# TIDA-010933-DCAC-TOP.net
KiCad netlist of a schematic drawn in Altium Designer
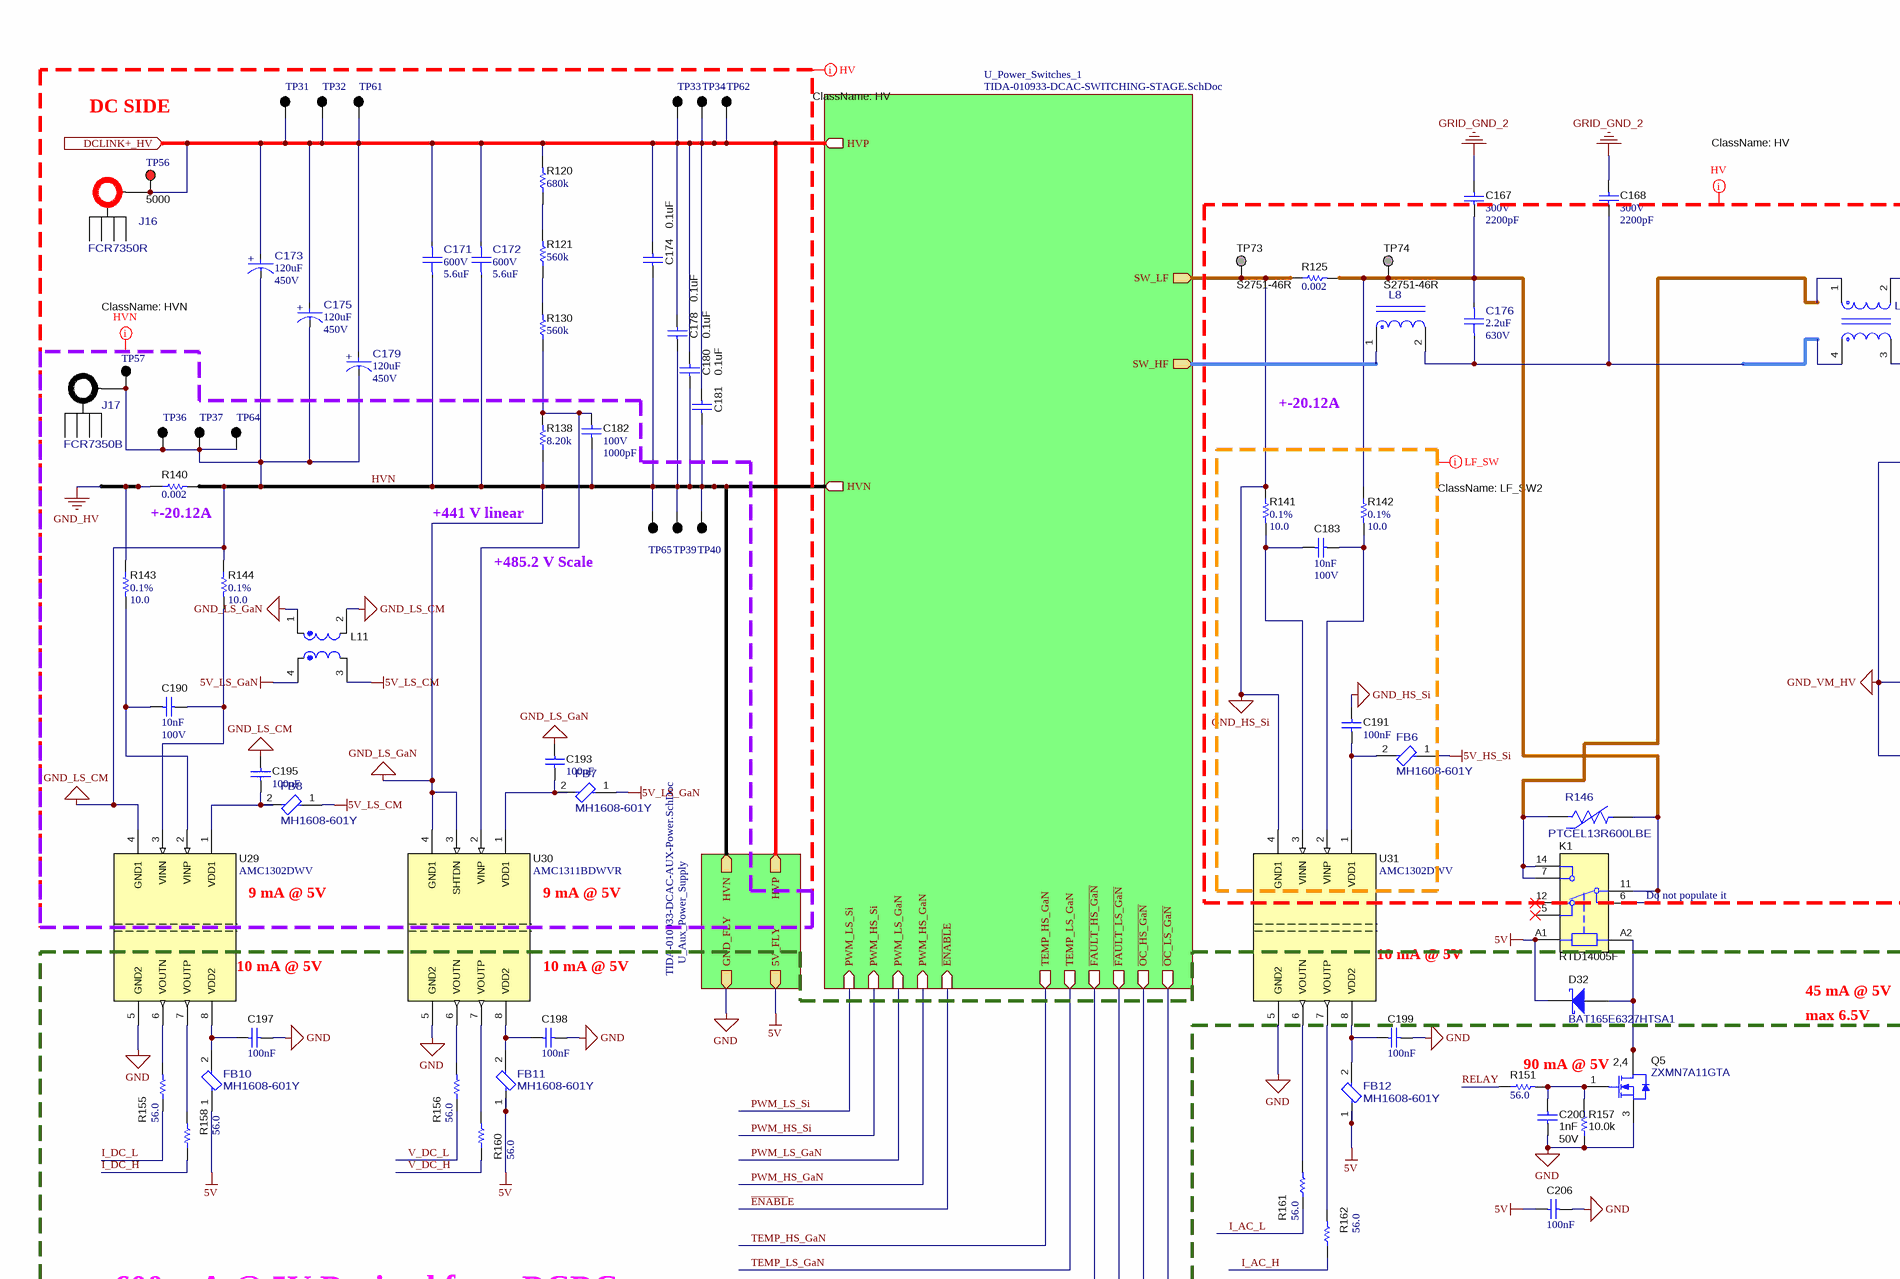
[diagram p0: TIDA-010933-DCAC-TOP.SchDoc, top left]
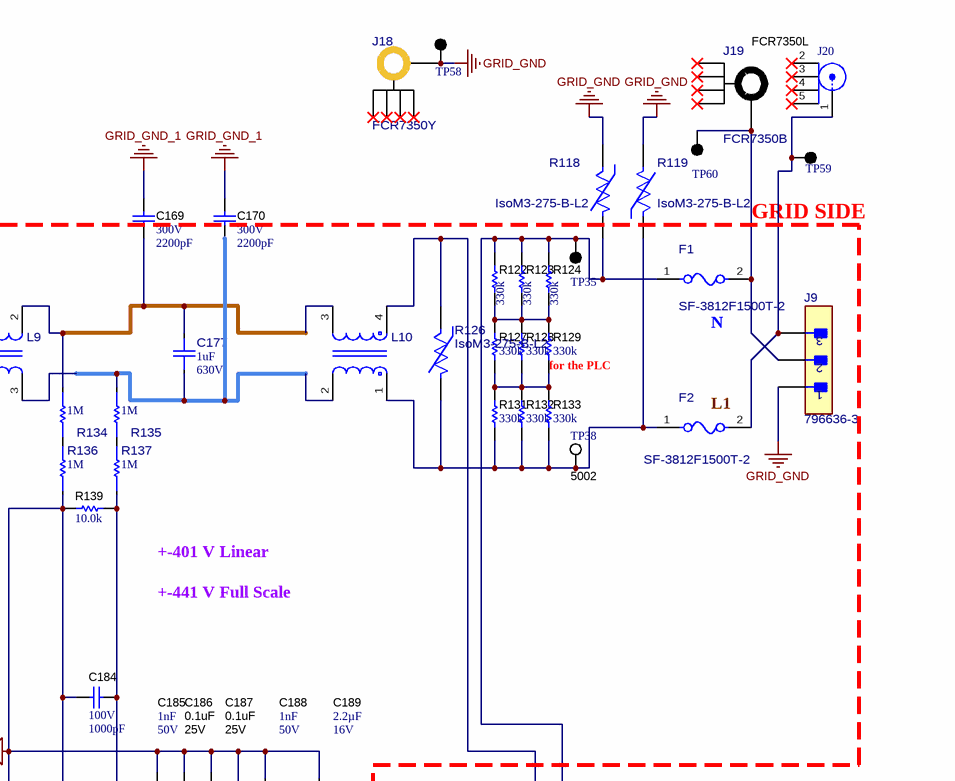
[diagram p1: TIDA-010933-DCAC-TOP.SchDoc, top right]
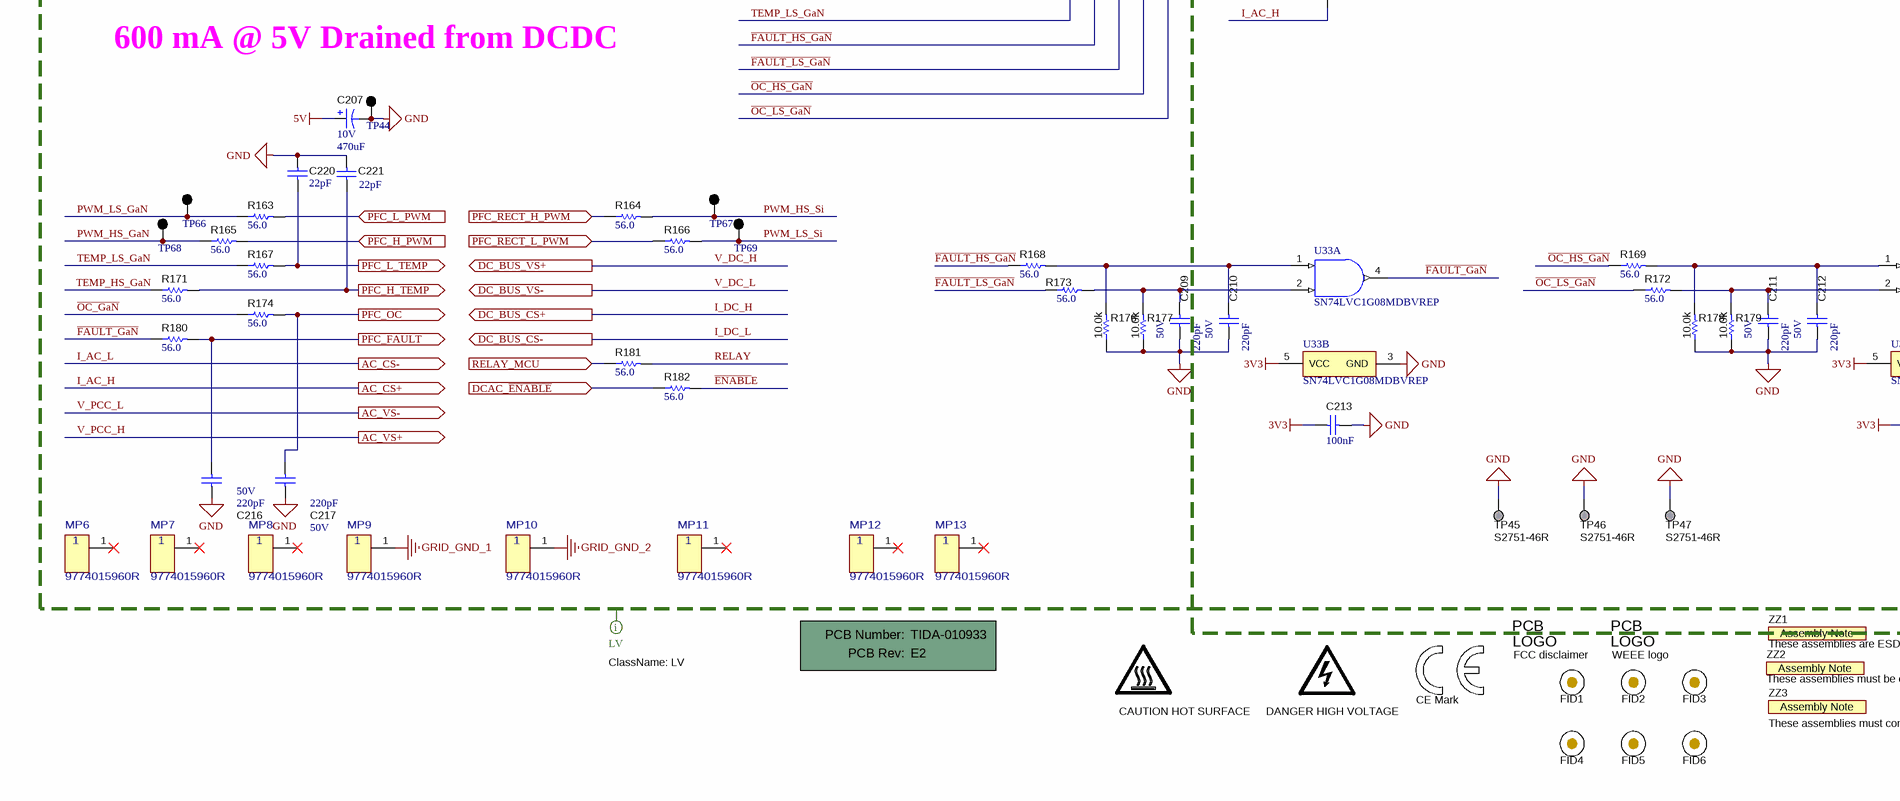
[diagram p2: TIDA-010933-DCAC-TOP.SchDoc, bottom left]
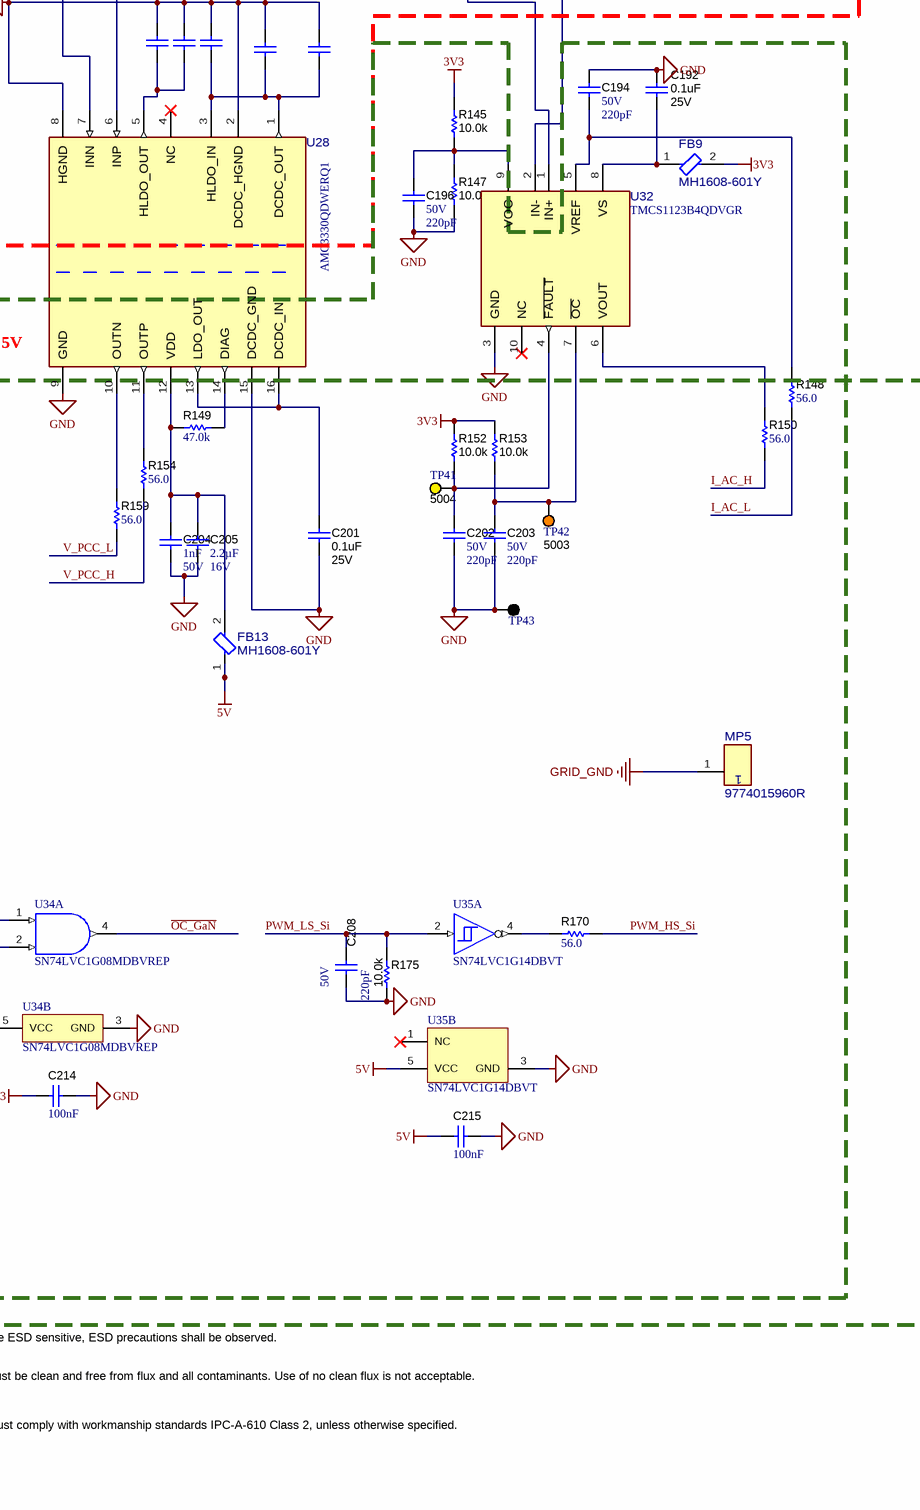
[diagram p3: TIDA-010933-DCAC-TOP.SchDoc, bottom right]

(export (version "E")
  (design (tool "Eeschema 10.0.6"))
  (components
    (comp (ref "!PCB1")
      (value "Printed Circuit Board")
      (fields (field (name "MANUFACTURER") "Any") (field (name "PUBLISHER") "Texas Instruments"))
      (libsource (lib "Altium Vault - TI") (part "PCB"))
    )
    (comp (ref "C167")
      (value "DE6E3KJ222MN3A")
      (footprint "E_900x700x900")
      (description "CAP, CERM, 2200 pF, 300 V, +/- 20%, E, TH, 2- Leads, Body 9x7mm, Pin Spacing 7.5mm")
      (fields
        (field (name "MANUFACTURER") "MuRata")
        (field (name "VDC_V") "300V")
        (field (name "VALUEDISPLAYED") "2200pF")
        (field (name "PUBLISHER") "Texas Instruments")
      )
      (libsource (lib "Altium Vault - TI") (part "Capacitor"))
    )
    (comp (ref "C168")
      (value "DE6E3KJ222MN3A")
      (footprint "E_900x700x900")
      (description "CAP, CERM, 2200 pF, 300 V, +/- 20%, E, TH, 2- Leads, Body 9x7mm, Pin Spacing 7.5mm")
      (fields
        (field (name "MANUFACTURER") "MuRata")
        (field (name "VDC_V") "300V")
        (field (name "VALUEDISPLAYED") "2200pF")
        (field (name "PUBLISHER") "Texas Instruments")
      )
      (libsource (lib "Altium Vault - TI") (part "Capacitor"))
    )
    (comp (ref "C169")
      (value "DE6E3KJ222MN3A")
      (footprint "E_900x700x900")
      (description "CAP, CERM, 2200 pF, 300 V, +/- 20%, E, TH, 2- Leads, Body 9x7mm, Pin Spacing 7.5mm")
      (fields
        (field (name "MANUFACTURER") "MuRata")
        (field (name "VDC_V") "300V")
        (field (name "VALUEDISPLAYED") "2200pF")
        (field (name "PUBLISHER") "Texas Instruments")
      )
      (libsource (lib "Altium Vault - TI") (part "Capacitor"))
    )
    (comp (ref "C170")
      (value "DE6E3KJ222MN3A")
      (footprint "E_900x700x900")
      (description "CAP, CERM, 2200 pF, 300 V, +/- 20%, E, TH, 2- Leads, Body 9x7mm, Pin Spacing 7.5mm")
      (fields
        (field (name "MANUFACTURER") "MuRata")
        (field (name "VDC_V") "300V")
        (field (name "VALUEDISPLAYED") "2200pF")
        (field (name "PUBLISHER") "Texas Instruments")
      )
      (libsource (lib "Altium Vault - TI") (part "Capacitor"))
    )
    (comp (ref "C171")
      (value "C4AQHBU4560P1XJ")
      (footprint "FP-C4AQHBU4560P1XJ_RADIAL-MFG")
      (description "5.6 µF Film Capacitor - 600V Polypropylene (PP), Metallized Radial")
      (fields
        (field (name "VDC_V") "600V")
        (field (name "VALUEDISPLAYED") "5.6uF")
        (field (name "MANUFACTURER") "KEMET")
        (field (name "MOUSER PART NUMBER") "80-C4AQHBU4560P1XJ")
      )
      (libsource (lib "Altium Vault - TI") (part "SYM-C4AQHBU4560P1XJ"))
    )
    (comp (ref "C172")
      (value "C4AQHBU4560P1XJ")
      (footprint "FP-C4AQHBU4560P1XJ_RADIAL-MFG")
      (description "5.6 µF Film Capacitor - 600V Polypropylene (PP), Metallized Radial")
      (fields
        (field (name "VDC_V") "600V")
        (field (name "VALUEDISPLAYED") "5.6uF")
        (field (name "MANUFACTURER") "KEMET")
        (field (name "MOUSER PART NUMBER") "80-C4AQHBU4560P1XJ")
      )
      (libsource (lib "Altium Vault - TI") (part "SYM-C4AQHBU4560P1XJ"))
    )
    (comp (ref "C173")
      (value "ALC80A121BD450")
      (footprint "FP-ALC80A121BD450_RADIAL-MFG")
      (description "ALC80, Aluminum Electrolytic, 120 uF, 20%, 450 VDC, -40/+105°C")
      (fields
        (field (name "MANUFACTURER") "KEMET")
        (field (name "VALUEDISPLAYED") "120uF")
        (field (name "VDC_V") "450V")
      )
      (libsource (lib "Altium Vault - TI") (part "SYM-ALC80A121BD450"))
    )
    (comp (ref "C174")
      (value "C1812W104KDRACTU")
      (footprint "1812_254")
      (description "CAP, CERM, 0.1 uF, 1000 V, +/- 10%, X7R, 1812")
      (fields
        (field (name "VALUEDISPLAYED") "0.1uF")
        (field (name "MANUFACTURER") "Kemet")
        (field (name "PUBLISHER") "Texas Instruments")
      )
      (libsource (lib "Altium Vault - TI") (part "Capacitor"))
    )
    (comp (ref "C175")
      (value "ALC80A121BD450")
      (footprint "FP-ALC80A121BD450_RADIAL-MFG")
      (description "ALC80, Aluminum Electrolytic, 120 uF, 20%, 450 VDC, -40/+105°C")
      (fields
        (field (name "MANUFACTURER") "KEMET")
        (field (name "VALUEDISPLAYED") "120uF")
        (field (name "VDC_V") "450V")
      )
      (libsource (lib "Altium Vault - TI") (part "SYM-ALC80A121BD450"))
    )
    (comp (ref "C176")
      (value "F863FL225K310Z")
      (footprint "FP-F863FL225K310Z_RADIAL-MFG")
      (description "2.2 µF Film Capacitor 310V Polypropylene (PP), Metallized Radial")
      (fields
        (field (name "MANUFACTURER") "KEMET")
        (field (name "VALUEDISPLAYED") "2.2uF")
        (field (name "VDC_V") "630V")
        (field (name "DIGIKEY PART NUMBER") "399-14811-ND")
      )
      (libsource (lib "Altium Vault - TI") (part "SYM-F863FL225K310Z"))
    )
    (comp (ref "C177")
      (value "F863DS105K310Z")
      (footprint "FP-F863DS105K310Z_RADIAL-MFG")
      (description "Cap Film 1uF 310VAC PP 10% (26.5 X 11 X 20mm) Dipped Radial 22.5mm 110°C Pizza Pack")
      (fields
        (field (name "MANUFACTURER") "KEMET")
        (field (name "VALUEDISPLAYED") "1uF")
        (field (name "VDC_V") "630V")
        (field (name "DIGIKEY PART NUMBER") "399-14809-ND")
      )
      (libsource (lib "Altium Vault - TI") (part "SYM-F863DS105K310Z"))
    )
    (comp (ref "C178")
      (value "C1812W104KDRACTU")
      (footprint "1812_254")
      (description "CAP, CERM, 0.1 uF, 1000 V, +/- 10%, X7R, 1812")
      (fields
        (field (name "VALUEDISPLAYED") "0.1uF")
        (field (name "MANUFACTURER") "Kemet")
        (field (name "PUBLISHER") "Texas Instruments")
      )
      (libsource (lib "Altium Vault - TI") (part "Capacitor"))
    )
    (comp (ref "C179")
      (value "ALC80A121BD450")
      (footprint "FP-ALC80A121BD450_RADIAL-MFG")
      (description "ALC80, Aluminum Electrolytic, 120 uF, 20%, 450 VDC, -40/+105°C")
      (fields
        (field (name "MANUFACTURER") "KEMET")
        (field (name "VALUEDISPLAYED") "120uF")
        (field (name "VDC_V") "450V")
      )
      (libsource (lib "Altium Vault - TI") (part "SYM-ALC80A121BD450"))
    )
    (comp (ref "C180")
      (value "C1812W104KDRACTU")
      (footprint "1812_254")
      (description "CAP, CERM, 0.1 uF, 1000 V, +/- 10%, X7R, 1812")
      (fields
        (field (name "VALUEDISPLAYED") "0.1uF")
        (field (name "MANUFACTURER") "Kemet")
        (field (name "PUBLISHER") "Texas Instruments")
      )
      (libsource (lib "Altium Vault - TI") (part "Capacitor"))
    )
    (comp (ref "C181")
      (value "C1812W104KDRACTU")
      (footprint "1812_254")
      (description "CAP, CERM, 0.1 uF, 1000 V, +/- 10%, X7R, 1812")
      (fields
        (field (name "VALUEDISPLAYED") "0.1uF")
        (field (name "MANUFACTURER") "Kemet")
        (field (name "PUBLISHER") "Texas Instruments")
      )
      (libsource (lib "Altium Vault - TI") (part "Capacitor"))
    )
    (comp (ref "C182")
      (value "GRM1885C2A102JA01D")
      (footprint "0603")
      (description "CAP, CERM, 1000 pF, 100 V, +/- 5%, C0G/NP0, 0603")
      (fields
        (field (name "MANUFACTURER") "MuRata")
        (field (name "VDC_V") "100V")
        (field (name "VALUEDISPLAYED") "1000pF")
        (field (name "PUBLISHER") "Texas Instruments")
      )
      (libsource (lib "Altium Vault - TI") (part "Capacitor"))
    )
    (comp (ref "C183")
      (value "CGA3E2X7R2A103K080AA")
      (footprint "0603")
      (description "CAP, CERM, 0.01 uF, 100 V, +/- 10%, X7R, AEC-Q200 Grade 1, 0603")
      (fields
        (field (name "MANUFACTURER") "TDK")
        (field (name "CAP_F") "10nF")
        (field (name "VDC_V") "100V")
        (field (name "PUBLISHER") "Texas Instruments")
      )
      (libsource (lib "Altium Vault - TI") (part "Capacitor"))
    )
    (comp (ref "C184")
      (value "GRM1885C2A102JA01D")
      (footprint "0603")
      (description "CAP, CERM, 1000 pF, 100 V, +/- 5%, C0G/NP0, 0603")
      (fields
        (field (name "MANUFACTURER") "MuRata")
        (field (name "VDC_V") "100V")
        (field (name "VALUEDISPLAYED") "1000pF")
        (field (name "PUBLISHER") "Texas Instruments")
      )
      (libsource (lib "Altium Vault - TI") (part "Capacitor"))
    )
    (comp (ref "C185")
      (value "C0603X102K5RACTU")
      (footprint "0603")
      (description "CAP, CERM, 1000 pF, 50 V, +/- 10%, X7R, 0603")
      (fields
        (field (name "MANUFACTURER") "Kemet")
        (field (name "CAP_F") "1nF")
        (field (name "VDC_V") "50V")
        (field (name "PUBLISHER") "Texas Instruments")
      )
      (libsource (lib "Altium Vault - TI") (part "Capacitor"))
    )
    (comp (ref "C186")
      (value "C0603X104K3RACTU")
      (footprint "0603")
      (description "CAP, CERM, 0.1 uF, 25 V, +/- 10%, X7R, 0603")
      (fields
        (field (name "VALUEDISPLAYED") "0.1uF")
        (field (name "MANUFACTURER") "Kemet")
        (field (name "VDC_V") "25V")
        (field (name "PUBLISHER") "Texas Instruments")
      )
      (libsource (lib "Altium Vault - TI") (part "Capacitor"))
    )
    (comp (ref "C187")
      (value "C0603X104K3RACTU")
      (footprint "0603")
      (description "CAP, CERM, 0.1 uF, 25 V, +/- 10%, X7R, 0603")
      (fields
        (field (name "VALUEDISPLAYED") "0.1uF")
        (field (name "MANUFACTURER") "Kemet")
        (field (name "VDC_V") "25V")
        (field (name "PUBLISHER") "Texas Instruments")
      )
      (libsource (lib "Altium Vault - TI") (part "Capacitor"))
    )
    (comp (ref "C188")
      (value "C0603X102K5RACTU")
      (footprint "0603")
      (description "CAP, CERM, 1000 pF, 50 V, +/- 10%, X7R, 0603")
      (fields
        (field (name "MANUFACTURER") "Kemet")
        (field (name "CAP_F") "1nF")
        (field (name "VDC_V") "50V")
        (field (name "PUBLISHER") "Texas Instruments")
      )
      (libsource (lib "Altium Vault - TI") (part "Capacitor"))
    )
    (comp (ref "C189")
      (value "EMK107BB7225KA-T")
      (footprint "0603")
      (description "CAP, CERM, 2.2 uF, 16 V, +/- 10%, X7R, 0603")
      (fields
        (field (name "MANUFACTURER") "Taiyo Yuden")
        (field (name "CAP_F") "2.2µF")
        (field (name "VDC_V") "16V")
        (field (name "PUBLISHER") "Texas Instruments")
      )
      (libsource (lib "Altium Vault - TI") (part "Capacitor"))
    )
    (comp (ref "C190")
      (value "CGA3E2X7R2A103K080AA")
      (footprint "0603")
      (description "CAP, CERM, 0.01 uF, 100 V, +/- 10%, X7R, AEC-Q200 Grade 1, 0603")
      (fields
        (field (name "MANUFACTURER") "TDK")
        (field (name "CAP_F") "10nF")
        (field (name "VDC_V") "100V")
        (field (name "PUBLISHER") "Texas Instruments")
      )
      (libsource (lib "Altium Vault - TI") (part "Capacitor"))
    )
    (comp (ref "C191")
      (value "06033C104JAT2A")
      (footprint "0603")
      (description "CAP, CERM, 0.1 uF, 25 V, +/- 5%, X7R, 0603")
      (fields
        (field (name "MANUFACTURER") "AVX")
        (field (name "CAP_F") "100nF")
        (field (name "PUBLISHER") "Texas Instruments")
      )
      (libsource (lib "Altium Vault - TI") (part "Capacitor"))
    )
    (comp (ref "C192")
      (value "C0603X104K3RACTU")
      (footprint "0603")
      (description "CAP, CERM, 0.1 uF, 25 V, +/- 10%, X7R, 0603")
      (fields
        (field (name "VALUEDISPLAYED") "0.1uF")
        (field (name "MANUFACTURER") "Kemet")
        (field (name "VDC_V") "25V")
        (field (name "PUBLISHER") "Texas Instruments")
      )
      (libsource (lib "Altium Vault - TI") (part "Capacitor"))
    )
    (comp (ref "C193")
      (value "06033C104JAT2A")
      (footprint "0603")
      (description "CAP, CERM, 0.1 uF, 25 V, +/- 5%, X7R, 0603")
      (fields
        (field (name "MANUFACTURER") "AVX")
        (field (name "CAP_F") "100nF")
        (field (name "PUBLISHER") "Texas Instruments")
      )
      (libsource (lib "Altium Vault - TI") (part "Capacitor"))
    )
    (comp (ref "C194")
      (value "C0603C221K5GACTU")
      (footprint "0603")
      (description "CAP, CERM, 220 pF, 50 V, +/- 10%, C0G/NP0, 0603")
      (fields
        (field (name "MANUFACTURER") "Kemet")
        (field (name "VDC_V") "50V")
        (field (name "VALUEDISPLAYED") "220pF")
        (field (name "PUBLISHER") "Texas Instruments")
      )
      (libsource (lib "Altium Vault - TI") (part "Capacitor"))
    )
    (comp (ref "C195")
      (value "06033C104JAT2A")
      (footprint "0603")
      (description "CAP, CERM, 0.1 uF, 25 V, +/- 5%, X7R, 0603")
      (fields
        (field (name "MANUFACTURER") "AVX")
        (field (name "CAP_F") "100nF")
        (field (name "PUBLISHER") "Texas Instruments")
      )
      (libsource (lib "Altium Vault - TI") (part "Capacitor"))
    )
    (comp (ref "C196")
      (value "C0603C221K5GACTU")
      (footprint "0603")
      (description "CAP, CERM, 220 pF, 50 V, +/- 10%, C0G/NP0, 0603")
      (fields
        (field (name "MANUFACTURER") "Kemet")
        (field (name "VDC_V") "50V")
        (field (name "VALUEDISPLAYED") "220pF")
        (field (name "PUBLISHER") "Texas Instruments")
      )
      (libsource (lib "Altium Vault - TI") (part "Capacitor"))
    )
    (comp (ref "C197")
      (value "06033C104JAT2A")
      (footprint "0603")
      (description "CAP, CERM, 0.1 uF, 25 V, +/- 5%, X7R, 0603")
      (fields
        (field (name "MANUFACTURER") "AVX")
        (field (name "CAP_F") "100nF")
        (field (name "PUBLISHER") "Texas Instruments")
      )
      (libsource (lib "Altium Vault - TI") (part "Capacitor"))
    )
    (comp (ref "C198")
      (value "06033C104JAT2A")
      (footprint "0603")
      (description "CAP, CERM, 0.1 uF, 25 V, +/- 5%, X7R, 0603")
      (fields
        (field (name "MANUFACTURER") "AVX")
        (field (name "CAP_F") "100nF")
        (field (name "PUBLISHER") "Texas Instruments")
      )
      (libsource (lib "Altium Vault - TI") (part "Capacitor"))
    )
    (comp (ref "C199")
      (value "06033C104JAT2A")
      (footprint "0603")
      (description "CAP, CERM, 0.1 uF, 25 V, +/- 5%, X7R, 0603")
      (fields
        (field (name "MANUFACTURER") "AVX")
        (field (name "CAP_F") "100nF")
        (field (name "PUBLISHER") "Texas Instruments")
      )
      (libsource (lib "Altium Vault - TI") (part "Capacitor"))
    )
    (comp (ref "C200")
      (value "C0603C102J5RACAUTO")
      (footprint "0603")
      (description "CAP, CERM, 1000 pF, 50 V, +/- 5%, X7R, AEC-Q200 Grade 1, 0603")
      (fields
        (field (name "MANUFACTURER") "Kemet")
        (field (name "CAP_F") "1nF")
        (field (name "VDC_V") "50V")
        (field (name "PUBLISHER") "Texas Instruments")
      )
      (libsource (lib "Altium Vault - TI") (part "Capacitor"))
    )
    (comp (ref "C201")
      (value "C0603X104K3RACTU")
      (footprint "0603")
      (description "CAP, CERM, 0.1 uF, 25 V, +/- 10%, X7R, 0603")
      (fields
        (field (name "VALUEDISPLAYED") "0.1uF")
        (field (name "MANUFACTURER") "Kemet")
        (field (name "VDC_V") "25V")
        (field (name "PUBLISHER") "Texas Instruments")
      )
      (libsource (lib "Altium Vault - TI") (part "Capacitor"))
    )
    (comp (ref "C202")
      (value "C0603C221K5GACTU")
      (footprint "0603")
      (description "CAP, CERM, 220 pF, 50 V, +/- 10%, C0G/NP0, 0603")
      (fields
        (field (name "MANUFACTURER") "Kemet")
        (field (name "VDC_V") "50V")
        (field (name "VALUEDISPLAYED") "220pF")
        (field (name "PUBLISHER") "Texas Instruments")
      )
      (libsource (lib "Altium Vault - TI") (part "Capacitor"))
    )
    (comp (ref "C203")
      (value "C0603C221K5GACTU")
      (footprint "0603")
      (description "CAP, CERM, 220 pF, 50 V, +/- 10%, C0G/NP0, 0603")
      (fields
        (field (name "MANUFACTURER") "Kemet")
        (field (name "VDC_V") "50V")
        (field (name "VALUEDISPLAYED") "220pF")
        (field (name "PUBLISHER") "Texas Instruments")
      )
      (libsource (lib "Altium Vault - TI") (part "Capacitor"))
    )
    (comp (ref "C204")
      (value "C0603X102K5RACTU")
      (footprint "0603")
      (description "CAP, CERM, 1000 pF, 50 V, +/- 10%, X7R, 0603")
      (fields
        (field (name "MANUFACTURER") "Kemet")
        (field (name "CAP_F") "1nF")
        (field (name "VDC_V") "50V")
        (field (name "PUBLISHER") "Texas Instruments")
      )
      (libsource (lib "Altium Vault - TI") (part "Capacitor"))
    )
    (comp (ref "C205")
      (value "EMK107BB7225KA-T")
      (footprint "0603")
      (description "CAP, CERM, 2.2 uF, 16 V, +/- 10%, X7R, 0603")
      (fields
        (field (name "MANUFACTURER") "Taiyo Yuden")
        (field (name "CAP_F") "2.2µF")
        (field (name "VDC_V") "16V")
        (field (name "PUBLISHER") "Texas Instruments")
      )
      (libsource (lib "Altium Vault - TI") (part "Capacitor"))
    )
    (comp (ref "C206")
      (value "06033C104JAT2A")
      (footprint "0603")
      (description "CAP, CERM, 0.1 uF, 25 V, +/- 5%, X7R, 0603")
      (fields
        (field (name "MANUFACTURER") "AVX")
        (field (name "CAP_F") "100nF")
        (field (name "PUBLISHER") "Texas Instruments")
      )
      (libsource (lib "Altium Vault - TI") (part "Capacitor"))
    )
    (comp (ref "C207")
      (value "TPSE477M010R0045")
      (footprint "7343-43")
      (description "CAP, TA, 470 uF, 10 V, +/- 20%, 0.045 ohm, SMD")
      (fields
        (field (name "MANUFACTURER") "AVX")
        (field (name "VDC_V") "10V")
        (field (name "VALUEDISPLAYED") "470uF")
        (field (name "PUBLISHER") "Texas Instruments")
      )
      (libsource (lib "Altium Vault - TI") (part "Cap_Polarized"))
    )
    (comp (ref "C208")
      (value "C0603C221K5GACTU")
      (footprint "0603")
      (description "CAP, CERM, 220 pF, 50 V, +/- 10%, C0G/NP0, 0603")
      (fields
        (field (name "MANUFACTURER") "Kemet")
        (field (name "VDC_V") "50V")
        (field (name "VALUEDISPLAYED") "220pF")
        (field (name "PUBLISHER") "Texas Instruments")
      )
      (libsource (lib "Altium Vault - TI") (part "Capacitor"))
    )
    (comp (ref "C209")
      (value "C0603C221K5GACTU")
      (footprint "0603")
      (description "CAP, CERM, 220 pF, 50 V, +/- 10%, C0G/NP0, 0603")
      (fields
        (field (name "MANUFACTURER") "Kemet")
        (field (name "VDC_V") "50V")
        (field (name "VALUEDISPLAYED") "220pF")
        (field (name "PUBLISHER") "Texas Instruments")
      )
      (libsource (lib "Altium Vault - TI") (part "Capacitor"))
    )
    (comp (ref "C210")
      (value "C0603C221K5GACTU")
      (footprint "0603")
      (description "CAP, CERM, 220 pF, 50 V, +/- 10%, C0G/NP0, 0603")
      (fields
        (field (name "MANUFACTURER") "Kemet")
        (field (name "VDC_V") "50V")
        (field (name "VALUEDISPLAYED") "220pF")
        (field (name "PUBLISHER") "Texas Instruments")
      )
      (libsource (lib "Altium Vault - TI") (part "Capacitor"))
    )
    (comp (ref "C211")
      (value "C0603C221K5GACTU")
      (footprint "0603")
      (description "CAP, CERM, 220 pF, 50 V, +/- 10%, C0G/NP0, 0603")
      (fields
        (field (name "MANUFACTURER") "Kemet")
        (field (name "VDC_V") "50V")
        (field (name "VALUEDISPLAYED") "220pF")
        (field (name "PUBLISHER") "Texas Instruments")
      )
      (libsource (lib "Altium Vault - TI") (part "Capacitor"))
    )
    (comp (ref "C212")
      (value "C0603C221K5GACTU")
      (footprint "0603")
      (description "CAP, CERM, 220 pF, 50 V, +/- 10%, C0G/NP0, 0603")
      (fields
        (field (name "MANUFACTURER") "Kemet")
        (field (name "VDC_V") "50V")
        (field (name "VALUEDISPLAYED") "220pF")
        (field (name "PUBLISHER") "Texas Instruments")
      )
      (libsource (lib "Altium Vault - TI") (part "Capacitor"))
    )
    (comp (ref "C213")
      (value "06033C104JAT2A")
      (footprint "0603")
      (description "CAP, CERM, 0.1 uF, 25 V, +/- 5%, X7R, 0603")
      (fields
        (field (name "MANUFACTURER") "AVX")
        (field (name "CAP_F") "100nF")
        (field (name "PUBLISHER") "Texas Instruments")
      )
      (libsource (lib "Altium Vault - TI") (part "Capacitor"))
    )
    (comp (ref "C214")
      (value "06033C104JAT2A")
      (footprint "0603")
      (description "CAP, CERM, 0.1 uF, 25 V, +/- 5%, X7R, 0603")
      (fields
        (field (name "MANUFACTURER") "AVX")
        (field (name "CAP_F") "100nF")
        (field (name "PUBLISHER") "Texas Instruments")
      )
      (libsource (lib "Altium Vault - TI") (part "Capacitor"))
    )
    (comp (ref "C215")
      (value "06033C104JAT2A")
      (footprint "0603")
      (description "CAP, CERM, 0.1 uF, 25 V, +/- 5%, X7R, 0603")
      (fields
        (field (name "MANUFACTURER") "AVX")
        (field (name "CAP_F") "100nF")
        (field (name "PUBLISHER") "Texas Instruments")
      )
      (libsource (lib "Altium Vault - TI") (part "Capacitor"))
    )
    (comp (ref "C216")
      (value "C0603C221K5GACTU")
      (footprint "0603")
      (description "CAP, CERM, 220 pF, 50 V, +/- 10%, C0G/NP0, 0603")
      (fields
        (field (name "MANUFACTURER") "Kemet")
        (field (name "VDC_V") "50V")
        (field (name "VALUEDISPLAYED") "220pF")
        (field (name "PUBLISHER") "Texas Instruments")
      )
      (libsource (lib "Altium Vault - TI") (part "Capacitor"))
    )
    (comp (ref "C217")
      (value "C0603C221K5GACTU")
      (footprint "0603")
      (description "CAP, CERM, 220 pF, 50 V, +/- 10%, C0G/NP0, 0603")
      (fields
        (field (name "MANUFACTURER") "Kemet")
        (field (name "VDC_V") "50V")
        (field (name "VALUEDISPLAYED") "220pF")
        (field (name "PUBLISHER") "Texas Instruments")
      )
      (libsource (lib "Altium Vault - TI") (part "Capacitor"))
    )
    (comp (ref "C220")
      (value "GRM1885C1H220JA01D")
      (footprint "0603")
      (description "CAP, CERM, 22 pF, 50 V, +/- 5%, C0G/NP0, 0603")
      (fields
        (field (name "MANUFACTURER") "MuRata")
        (field (name "VALUEDISPLAYED") "22pF")
        (field (name "PUBLISHER") "Texas Instruments")
      )
      (libsource (lib "Altium Vault - TI") (part "Capacitor"))
    )
    (comp (ref "C221")
      (value "GRM1885C1H220JA01D")
      (footprint "0603")
      (description "CAP, CERM, 22 pF, 50 V, +/- 5%, C0G/NP0, 0603")
      (fields
        (field (name "MANUFACTURER") "MuRata")
        (field (name "VALUEDISPLAYED") "22pF")
        (field (name "PUBLISHER") "Texas Instruments")
      )
      (libsource (lib "Altium Vault - TI") (part "Capacitor"))
    )
    (comp (ref "D32")
      (value "BAT165E6327HTSA1")
      (footprint "SOD-323")
      (description "Diode, Schottky, 40 V, 0.75 A, AEC-Q101, SOD-323")
      (fields (field (name "MANUFACTURER") "Infineon Technologies"))
      (libsource (lib "Altium Vault - TI") (part "DIODE_SCHOTTKY"))
    )
    (comp (ref "F1")
      (value "SF-3812F1500T-2")
      (footprint "FP-SF-3812F1500T-2_3812-MFG")
      (fields
        (field (name "MANUFACTURER") "Bourns")
        (field (name "DIGIKEY PART NUMBER") "SF-3812F1500T-2CT-ND")
        (field (name "MOUSER PART NUMBER") "652-SF-3812F1500T-2")
      )
      (libsource (lib "Altium Vault - TI") (part "SYM-SF-3812F1500T-2"))
    )
    (comp (ref "F2")
      (value "SF-3812F1500T-2")
      (footprint "FP-SF-3812F1500T-2_3812-MFG")
      (fields
        (field (name "MANUFACTURER") "Bourns")
        (field (name "DIGIKEY PART NUMBER") "SF-3812F1500T-2CT-ND")
        (field (name "MOUSER PART NUMBER") "652-SF-3812F1500T-2")
      )
      (libsource (lib "Altium Vault - TI") (part "SYM-SF-3812F1500T-2"))
    )
    (comp (ref "FB6")
      (value "MH1608-601Y")
      (footprint "FP-MH1608-601Y_0603-MFG")
      (description "600 Ohms @ 100 MHz 1 Power, Signal Line Ferrite Bead 0603 (1608 Metric) 1A 200mOhm")
      (fields (field (name "MANUFACTURER") "Bourns") (field (name "DIGIKEY PART NUMBER") "MH1608-601YCT-ND"))
      (libsource (lib "Altium Vault - TI") (part "SYM-MH1608-601Y"))
    )
    (comp (ref "FB7")
      (value "MH1608-601Y")
      (footprint "FP-MH1608-601Y_0603-MFG")
      (description "600 Ohms @ 100 MHz 1 Power, Signal Line Ferrite Bead 0603 (1608 Metric) 1A 200mOhm")
      (fields (field (name "MANUFACTURER") "Bourns") (field (name "DIGIKEY PART NUMBER") "MH1608-601YCT-ND"))
      (libsource (lib "Altium Vault - TI") (part "SYM-MH1608-601Y"))
    )
    (comp (ref "FB8")
      (value "MH1608-601Y")
      (footprint "FP-MH1608-601Y_0603-MFG")
      (description "600 Ohms @ 100 MHz 1 Power, Signal Line Ferrite Bead 0603 (1608 Metric) 1A 200mOhm")
      (fields (field (name "MANUFACTURER") "Bourns") (field (name "DIGIKEY PART NUMBER") "MH1608-601YCT-ND"))
      (libsource (lib "Altium Vault - TI") (part "SYM-MH1608-601Y"))
    )
    (comp (ref "FB9")
      (value "MH1608-601Y")
      (footprint "FP-MH1608-601Y_0603-MFG")
      (description "600 Ohms @ 100 MHz 1 Power, Signal Line Ferrite Bead 0603 (1608 Metric) 1A 200mOhm")
      (fields (field (name "MANUFACTURER") "Bourns") (field (name "DIGIKEY PART NUMBER") "MH1608-601YCT-ND"))
      (libsource (lib "Altium Vault - TI") (part "SYM-MH1608-601Y"))
    )
    (comp (ref "FB10")
      (value "MH1608-601Y")
      (footprint "FP-MH1608-601Y_0603-MFG")
      (description "600 Ohms @ 100 MHz 1 Power, Signal Line Ferrite Bead 0603 (1608 Metric) 1A 200mOhm")
      (fields (field (name "MANUFACTURER") "Bourns") (field (name "DIGIKEY PART NUMBER") "MH1608-601YCT-ND"))
      (libsource (lib "Altium Vault - TI") (part "SYM-MH1608-601Y"))
    )
    (comp (ref "FB11")
      (value "MH1608-601Y")
      (footprint "FP-MH1608-601Y_0603-MFG")
      (description "600 Ohms @ 100 MHz 1 Power, Signal Line Ferrite Bead 0603 (1608 Metric) 1A 200mOhm")
      (fields (field (name "MANUFACTURER") "Bourns") (field (name "DIGIKEY PART NUMBER") "MH1608-601YCT-ND"))
      (libsource (lib "Altium Vault - TI") (part "SYM-MH1608-601Y"))
    )
    (comp (ref "FB12")
      (value "MH1608-601Y")
      (footprint "FP-MH1608-601Y_0603-MFG")
      (description "600 Ohms @ 100 MHz 1 Power, Signal Line Ferrite Bead 0603 (1608 Metric) 1A 200mOhm")
      (fields (field (name "MANUFACTURER") "Bourns") (field (name "DIGIKEY PART NUMBER") "MH1608-601YCT-ND"))
      (libsource (lib "Altium Vault - TI") (part "SYM-MH1608-601Y"))
    )
    (comp (ref "FB13")
      (value "MH1608-601Y")
      (footprint "FP-MH1608-601Y_0603-MFG")
      (description "600 Ohms @ 100 MHz 1 Power, Signal Line Ferrite Bead 0603 (1608 Metric) 1A 200mOhm")
      (fields (field (name "MANUFACTURER") "Bourns") (field (name "DIGIKEY PART NUMBER") "MH1608-601YCT-ND"))
      (libsource (lib "Altium Vault - TI") (part "SYM-MH1608-601Y"))
    )
    (comp (ref "FID1")
      (value "Fiducial")
      (footprint "Fiducial6.4-20")
      (description "Fiducial mark.  There is nothing to buy or mount.")
      (libsource (lib "Altium Vault - TI") (part "CMP-0077181-1"))
    )
    (comp (ref "FID2")
      (value "Fiducial")
      (footprint "Fiducial6.4-20")
      (description "Fiducial mark.  There is nothing to buy or mount.")
      (libsource (lib "Altium Vault - TI") (part "CMP-0077181-1"))
    )
    (comp (ref "FID3")
      (value "Fiducial")
      (footprint "Fiducial6.4-20")
      (description "Fiducial mark.  There is nothing to buy or mount.")
      (libsource (lib "Altium Vault - TI") (part "CMP-0077181-1"))
    )
    (comp (ref "FID4")
      (value "Fiducial")
      (footprint "Fiducial6.4-20")
      (description "Fiducial mark.  There is nothing to buy or mount.")
      (libsource (lib "Altium Vault - TI") (part "CMP-0077181-1"))
    )
    (comp (ref "FID5")
      (value "Fiducial")
      (footprint "Fiducial6.4-20")
      (description "Fiducial mark.  There is nothing to buy or mount.")
      (libsource (lib "Altium Vault - TI") (part "CMP-0077181-1"))
    )
    (comp (ref "FID6")
      (value "Fiducial")
      (footprint "Fiducial6.4-20")
      (description "Fiducial mark.  There is nothing to buy or mount.")
      (libsource (lib "Altium Vault - TI") (part "CMP-0077181-1"))
    )
    (comp (ref "J9")
      (value "796636-3")
      (footprint "FP-796636-3_HDR3-MFG")
      (fields
        (field (name "MANUFACTURER") "TE Connectivity")
        (field (name "DIGIKEY PART NUMBER") "A98423-ND")
        (field (name "MOUSER PART NUMBER") "571-796636-3")
      )
      (libsource (lib "Altium Vault - TI") (part "SYM-796636-3"))
    )
    (comp (ref "J16")
      (value "FCR7350R")
      (footprint "FP-FCR7350R_CONN_BANANA_JACK-MFG")
      (description "Banana Jack Connector Standard Banana Solder Red")
      (fields
        (field (name "MANUFACTURER") "CLIFF Electronic Components")
        (field (name "DIGIKEY PART NUMBER") "4654-FCR7350R-ND")
      )
      (libsource (lib "Altium Vault - TI") (part "SYM-FCR7350R"))
    )
    (comp (ref "J17")
      (value "FCR7350B")
      (footprint "FP-FCR7350B_CONN_BANANA_JACK-MFG")
      (description "Banana Jack Connector Standard Banana Solder Black")
      (fields
        (field (name "MANUFACTURER") "CLIFF Electronic Components")
        (field (name "DIGIKEY PART NUMBER") "4654-FCR7350B-ND")
      )
      (libsource (lib "Altium Vault - TI") (part "SYM-FCR7350B"))
    )
    (comp (ref "J18")
      (value "FCR7350Y")
      (footprint "FP-FCR7350Y_CONN_BANANA_JACK-MFG")
      (description "Banana Jack Connector Standard Banana Solder Yellow")
      (fields
        (field (name "MANUFACTURER") "CLIFF Electronic Components")
        (field (name "DIGIKEY PART NUMBER") "4654-FCR7350Y-ND")
      )
      (libsource (lib "Altium Vault - TI") (part "SYM-FCR7350Y"))
    )
    (comp (ref "J19")
      (value "FCR7350B")
      (footprint "FP-FCR7350B_CONN_BANANA_JACK-MFG")
      (description "Banana Jack Connector Standard Banana Solder Black")
      (fields
        (field (name "MANUFACTURER") "CLIFF Electronic Components")
        (field (name "DIGIKEY PART NUMBER") "4654-FCR7350B-ND")
      )
      (libsource (lib "Altium Vault - TI") (part "SYM-FCR7350B"))
    )
    (comp (ref "J20")
      (value "FCR7350L")
      (footprint "FP-FCR7350L_CONN_BANANA_JACK-MFG")
      (description "Banana Test Connector, 4mm, Socket, PCB Mount, 24 A, 1 kV, Gold Plated Contacts, Blue")
      (fields (field (name "MANUFACTURER") "CLIFF Electronic Components"))
      (libsource (lib "Altium Vault - TI") (part "SMA_Contact1_GND2345"))
    )
    (comp (ref "K1")
      (value "RTD14005F")
      (footprint "Relay_RTD14005F")
      (description "Relay, SPDT (1 Form C), 16 A, 5 V, TH")
      (fields (field (name "MANUFACTURER") "TE Connectivity"))
      (libsource (lib "Altium Vault - TI") (part "Relay_RTD14005F"))
    )
    (comp (ref "L8")
      (value "145450")
      (footprint "FP-D6746_PTH_59MM5_50MM0-MFG")
      (description "PFC Inductor")
      (fields (field (name "MANUFACTURER") "Bourns") (field (name "PART NUMBER") "D6746"))
      (libsource (lib "Altium Vault - TI") (part "SYM-D6746"))
    )
    (comp (ref "L9")
      (value "047690")
      (footprint "FP-D6744_PTH_CMC_38MM0-MFG")
      (description "Common Mode Chokes 4mH 50mohm 250kHz")
      (fields (field (name "MANUFACTURER") "Bourns") (field (name "PART NUMBER") "D6744"))
      (libsource (lib "Altium Vault - TI") (part "SYM-D6744"))
    )
    (comp (ref "L10")
      (value "047690")
      (footprint "FP-D6744_PTH_CMC_38MM0-MFG")
      (description "Common Mode Chokes 4mH 50mohm 250kHz")
      (fields (field (name "MANUFACTURER") "Bourns") (field (name "PART NUMBER") "D6744"))
      (libsource (lib "Altium Vault - TI") (part "SYM-D6744"))
    )
    (comp (ref "L11")
      (value "SRF2012-361YA")
      (footprint "SRF2012A")
      (description "Inductor, Wirewound, Ferrite, 0.3 A, 0.45 ohm, SMD")
      (fields (field (name "MANUFACTURER") "Bourns") (field (name "PUBLISHER") "Texas Instruments"))
      (libsource (lib "Altium Vault - TI") (part "Inductor_Polarity_Dual_12_43"))
    )
    (comp (ref "Logo1")
      (value "FCC disclaimer")
      (footprint "FCC_disclaimer_stacked")
      (description "FCC_disclaimer")
      (fields (field (name "PUBLISHER") "Texas Instruments"))
      (libsource (lib "Altium Vault - TI") (part "CMP-0074847-1"))
    )
    (comp (ref "Logo2")
      (value "WEEE logo")
      (footprint "WEEE_Minimum")
      (libsource (lib "Altium Vault - TI") (part "Logo"))
    )
    (comp (ref "LOGO3")
      (value "CAUTION HOT SURFACE")
      (footprint "IEC_HotSurface_Small")
      (description "IEC 61010-1 Hot Surface Warning")
      (fields (field (name "SYMBOLCREATOR") "a0412235") (field (name "PUBLISHER") "Texas Instruments"))
      (libsource (lib "Altium Vault - TI") (part "CMP-0074837-1"))
    )
    (comp (ref "LOGO4")
      (value "DANGER HIGH VOLTAGE")
      (footprint "IEC_HighVoltage_Small")
      (description "IEC 61010-1 High Voltage Warning")
      (fields (field (name "SYMBOLCREATOR") "a0412235") (field (name "PUBLISHER") "Texas Instruments"))
      (libsource (lib "Altium Vault - TI") (part "CMP-0074835-1"))
    )
    (comp (ref "Logo5")
      (value "CE Mark")
      (footprint "CE_Mark_5mm")
      (fields (field (name "SYMBOLCREATOR") "a0412235") (field (name "PUBLISHER") "Texas Instruments"))
      (libsource (lib "Altium Vault - TI") (part "CE Mark"))
    )
    (comp (ref "MP5")
      (value "9774015960R")
      (footprint "FP-9774015960R_ROUND_SPACER_6MM0-MFG")
      (description "Round Spacer Unthreaded Steel 0.059\" (1.50mm)")
      (fields
        (field (name "MANUFACTURER") "Wurth Electronics")
        (field (name "DIGIKEY PART NUMBER") "732-7071-1-ND")
      )
      (libsource (lib "") (part "SYM-9774015960R_1"))
    )
    (comp (ref "MP6")
      (value "9774015960R")
      (footprint "FP-9774015960R_ROUND_SPACER_6MM0-MFG")
      (description "Round Spacer Unthreaded Steel 0.059\" (1.50mm)")
      (fields
        (field (name "MANUFACTURER") "Wurth Electronics")
        (field (name "DIGIKEY PART NUMBER") "732-7071-1-ND")
      )
      (libsource (lib "Altium Vault - TI") (part "SYM-9774015960R"))
    )
    (comp (ref "MP7")
      (value "9774015960R")
      (footprint "FP-9774015960R_ROUND_SPACER_6MM0-MFG")
      (description "Round Spacer Unthreaded Steel 0.059\" (1.50mm)")
      (fields
        (field (name "MANUFACTURER") "Wurth Electronics")
        (field (name "DIGIKEY PART NUMBER") "732-7071-1-ND")
      )
      (libsource (lib "Altium Vault - TI") (part "SYM-9774015960R"))
    )
    (comp (ref "MP8")
      (value "9774015960R")
      (footprint "FP-9774015960R_ROUND_SPACER_6MM0-MFG")
      (description "Round Spacer Unthreaded Steel 0.059\" (1.50mm)")
      (fields
        (field (name "MANUFACTURER") "Wurth Electronics")
        (field (name "DIGIKEY PART NUMBER") "732-7071-1-ND")
      )
      (libsource (lib "Altium Vault - TI") (part "SYM-9774015960R"))
    )
    (comp (ref "MP9")
      (value "9774015960R")
      (footprint "FP-9774015960R_ROUND_SPACER_6MM0-MFG")
      (description "Round Spacer Unthreaded Steel 0.059\" (1.50mm)")
      (fields
        (field (name "MANUFACTURER") "Wurth Electronics")
        (field (name "DIGIKEY PART NUMBER") "732-7071-1-ND")
      )
      (libsource (lib "Altium Vault - TI") (part "SYM-9774015960R"))
    )
    (comp (ref "MP10")
      (value "9774015960R")
      (footprint "FP-9774015960R_ROUND_SPACER_6MM0-MFG")
      (description "Round Spacer Unthreaded Steel 0.059\" (1.50mm)")
      (fields
        (field (name "MANUFACTURER") "Wurth Electronics")
        (field (name "DIGIKEY PART NUMBER") "732-7071-1-ND")
      )
      (libsource (lib "Altium Vault - TI") (part "SYM-9774015960R"))
    )
    (comp (ref "MP11")
      (value "9774015960R")
      (footprint "FP-9774015960R_ROUND_SPACER_6MM0-MFG")
      (description "Round Spacer Unthreaded Steel 0.059\" (1.50mm)")
      (fields
        (field (name "MANUFACTURER") "Wurth Electronics")
        (field (name "DIGIKEY PART NUMBER") "732-7071-1-ND")
      )
      (libsource (lib "Altium Vault - TI") (part "SYM-9774015960R"))
    )
    (comp (ref "MP12")
      (value "9774015960R")
      (footprint "FP-9774015960R_ROUND_SPACER_6MM0-MFG")
      (description "Round Spacer Unthreaded Steel 0.059\" (1.50mm)")
      (fields
        (field (name "MANUFACTURER") "Wurth Electronics")
        (field (name "DIGIKEY PART NUMBER") "732-7071-1-ND")
      )
      (libsource (lib "Altium Vault - TI") (part "SYM-9774015960R"))
    )
    (comp (ref "MP13")
      (value "9774015960R")
      (footprint "FP-9774015960R_ROUND_SPACER_6MM0-MFG")
      (description "Round Spacer Unthreaded Steel 0.059\" (1.50mm)")
      (fields
        (field (name "MANUFACTURER") "Wurth Electronics")
        (field (name "DIGIKEY PART NUMBER") "732-7071-1-ND")
      )
      (libsource (lib "Altium Vault - TI") (part "SYM-9774015960R"))
    )
    (comp (ref "Q5")
      (value "ZXMN7A11GTA")
      (footprint "SOT-223")
      (description "MOSFET, N-CH, 70 V, 3.8 A, AEC-Q101, SOT-223")
      (fields (field (name "MANUFACTURER") "Diodes Inc.") (field (name "PUBLISHER") "Texas Instruments"))
      (libsource (lib "Altium Vault - TI") (part "MOSFET_N_D24G1S3"))
    )
    (comp (ref "R118")
      (value "IsoM3-275-B-L2")
      (footprint "FP-IsoM3-275-B-L2_RADIAL-MFG")
      (description "3 kA Varistor 1 Circuit Through Hole Disc 13.2mm")
      (fields
        (field (name "DIGIKEY PART NUMBER") "118-ISOM3-275-B-L2-ND")
        (field (name "MANUFACTURER") "Bourns")
      )
      (libsource (lib "Altium Vault - TI") (part "SYM-IsoM3-275-B-L2"))
    )
    (comp (ref "R119")
      (value "IsoM3-275-B-L2")
      (footprint "FP-IsoM3-275-B-L2_RADIAL-MFG")
      (description "3 kA Varistor 1 Circuit Through Hole Disc 13.2mm")
      (fields
        (field (name "DIGIKEY PART NUMBER") "118-ISOM3-275-B-L2-ND")
        (field (name "MANUFACTURER") "Bourns")
      )
      (libsource (lib "Altium Vault - TI") (part "SYM-IsoM3-275-B-L2"))
    )
    (comp (ref "R120")
      (value "TNPV1206680KBEEN")
      (footprint "TNPV1206")
      (description "RES, 680 k, 0.1%, 1 W, 1206")
      (fields
        (field (name "MANUFACTURER") "Vishay Draloric")
        (field (name "VALUEDISPLAYED") "680k")
        (field (name "PUBLISHER") "Texas Instruments")
      )
      (libsource (lib "Altium Vault - TI") (part "Resistor"))
    )
    (comp (ref "R121")
      (value "TNPV1206560KBEEN")
      (footprint "TNPV1206")
      (description "RES, 560 k, 0.1%, 1 W, 1206")
      (fields
        (field (name "MANUFACTURER") "Vishay Draloric")
        (field (name "VALUEDISPLAYED") "560k")
        (field (name "PUBLISHER") "Texas Instruments")
      )
      (libsource (lib "Altium Vault - TI") (part "Resistor"))
    )
    (comp (ref "R122")
      (value "CRCW1206330KJNEA")
      (footprint "1206")
      (description "RES, 330 k, 5%, 0.25 W, AEC-Q200 Grade 0, 1206")
      (fields (field (name "MANUFACTURER") "Vishay-Dale") (field (name "VALUEDISPLAYED") "330k"))
      (libsource (lib "Altium Vault - TI") (part "Resistor"))
    )
    (comp (ref "R123")
      (value "CRCW1206330KJNEA")
      (footprint "1206")
      (description "RES, 330 k, 5%, 0.25 W, AEC-Q200 Grade 0, 1206")
      (fields (field (name "MANUFACTURER") "Vishay-Dale") (field (name "VALUEDISPLAYED") "330k"))
      (libsource (lib "Altium Vault - TI") (part "Resistor"))
    )
    (comp (ref "R124")
      (value "CRCW1206330KJNEA")
      (footprint "1206")
      (description "RES, 330 k, 5%, 0.25 W, AEC-Q200 Grade 0, 1206")
      (fields (field (name "MANUFACTURER") "Vishay-Dale") (field (name "VALUEDISPLAYED") "330k"))
      (libsource (lib "Altium Vault - TI") (part "Resistor"))
    )
    (comp (ref "R125")
      (value "CRF1206-FZ-R002ELF")
      (footprint "1206")
      (description "RES, 0.002, 1%, 1 W, AEC-Q200 Grade 0, 1206")
      (fields (field (name "MANUFACTURER") "Bourns") (field (name "VALUEDISPLAYED") "0.002"))
      (libsource (lib "Altium Vault - TI") (part "Resistor"))
    )
    (comp (ref "R126")
      (value "IsoM3-275-B-L2")
      (footprint "FP-IsoM3-275-B-L2_RADIAL-MFG")
      (description "3 kA Varistor 1 Circuit Through Hole Disc 13.2mm")
      (fields
        (field (name "DIGIKEY PART NUMBER") "118-ISOM3-275-B-L2-ND")
        (field (name "MANUFACTURER") "Bourns")
      )
      (libsource (lib "Altium Vault - TI") (part "SYM-IsoM3-275-B-L2"))
    )
    (comp (ref "R127")
      (value "CRCW1206330KJNEA")
      (footprint "1206")
      (description "RES, 330 k, 5%, 0.25 W, AEC-Q200 Grade 0, 1206")
      (fields (field (name "MANUFACTURER") "Vishay-Dale") (field (name "VALUEDISPLAYED") "330k"))
      (libsource (lib "Altium Vault - TI") (part "Resistor"))
    )
    (comp (ref "R128")
      (value "CRCW1206330KJNEA")
      (footprint "1206")
      (description "RES, 330 k, 5%, 0.25 W, AEC-Q200 Grade 0, 1206")
      (fields (field (name "MANUFACTURER") "Vishay-Dale") (field (name "VALUEDISPLAYED") "330k"))
      (libsource (lib "Altium Vault - TI") (part "Resistor"))
    )
    (comp (ref "R129")
      (value "CRCW1206330KJNEA")
      (footprint "1206")
      (description "RES, 330 k, 5%, 0.25 W, AEC-Q200 Grade 0, 1206")
      (fields (field (name "MANUFACTURER") "Vishay-Dale") (field (name "VALUEDISPLAYED") "330k"))
      (libsource (lib "Altium Vault - TI") (part "Resistor"))
    )
    (comp (ref "R130")
      (value "TNPV1206560KBEEN")
      (footprint "TNPV1206")
      (description "RES, 560 k, 0.1%, 1 W, 1206")
      (fields
        (field (name "MANUFACTURER") "Vishay Draloric")
        (field (name "VALUEDISPLAYED") "560k")
        (field (name "PUBLISHER") "Texas Instruments")
      )
      (libsource (lib "Altium Vault - TI") (part "Resistor"))
    )
    (comp (ref "R131")
      (value "CRCW1206330KJNEA")
      (footprint "1206")
      (description "RES, 330 k, 5%, 0.25 W, AEC-Q200 Grade 0, 1206")
      (fields (field (name "MANUFACTURER") "Vishay-Dale") (field (name "VALUEDISPLAYED") "330k"))
      (libsource (lib "Altium Vault - TI") (part "Resistor"))
    )
    (comp (ref "R132")
      (value "CRCW1206330KJNEA")
      (footprint "1206")
      (description "RES, 330 k, 5%, 0.25 W, AEC-Q200 Grade 0, 1206")
      (fields (field (name "MANUFACTURER") "Vishay-Dale") (field (name "VALUEDISPLAYED") "330k"))
      (libsource (lib "Altium Vault - TI") (part "Resistor"))
    )
    (comp (ref "R133")
      (value "CRCW1206330KJNEA")
      (footprint "1206")
      (description "RES, 330 k, 5%, 0.25 W, AEC-Q200 Grade 0, 1206")
      (fields (field (name "MANUFACTURER") "Vishay-Dale") (field (name "VALUEDISPLAYED") "330k"))
      (libsource (lib "Altium Vault - TI") (part "Resistor"))
    )
    (comp (ref "R134")
      (value "RGV3216P-1004-B-T1")
      (footprint "FP-RGV3216P-1004-B-T1_1206-MFG")
      (fields
        (field (name "RES_OHM") "1M")
        (field (name "DIGIKEY PART NUMBER") "408-RGV3216P-1004-B-T1CT-ND")
        (field (name "MOUSER PART NUMBER") "754-RGV3216P-1004BT1")
        (field (name "MANUFACTURER") "Susumu")
      )
      (libsource (lib "Altium Vault - TI") (part "SYM-RGV3216P-1004-B-T1"))
    )
    (comp (ref "R135")
      (value "RGV3216P-1004-B-T1")
      (footprint "FP-RGV3216P-1004-B-T1_1206-MFG")
      (fields
        (field (name "RES_OHM") "1M")
        (field (name "DIGIKEY PART NUMBER") "408-RGV3216P-1004-B-T1CT-ND")
        (field (name "MOUSER PART NUMBER") "754-RGV3216P-1004BT1")
        (field (name "MANUFACTURER") "Susumu")
      )
      (libsource (lib "Altium Vault - TI") (part "SYM-RGV3216P-1004-B-T1"))
    )
    (comp (ref "R136")
      (value "RGV3216P-1004-B-T1")
      (footprint "FP-RGV3216P-1004-B-T1_1206-MFG")
      (fields
        (field (name "RES_OHM") "1M")
        (field (name "DIGIKEY PART NUMBER") "408-RGV3216P-1004-B-T1CT-ND")
        (field (name "MOUSER PART NUMBER") "754-RGV3216P-1004BT1")
        (field (name "MANUFACTURER") "Susumu")
      )
      (libsource (lib "Altium Vault - TI") (part "SYM-RGV3216P-1004-B-T1"))
    )
    (comp (ref "R137")
      (value "RGV3216P-1004-B-T1")
      (footprint "FP-RGV3216P-1004-B-T1_1206-MFG")
      (fields
        (field (name "RES_OHM") "1M")
        (field (name "DIGIKEY PART NUMBER") "408-RGV3216P-1004-B-T1CT-ND")
        (field (name "MOUSER PART NUMBER") "754-RGV3216P-1004BT1")
        (field (name "MANUFACTURER") "Susumu")
      )
      (libsource (lib "Altium Vault - TI") (part "SYM-RGV3216P-1004-B-T1"))
    )
    (comp (ref "R138")
      (value "RG1608P-822-B-T5")
      (footprint "0603")
      (description "RES, 8.20 k, 0.1%, 0.1 W, 0603")
      (fields
        (field (name "MANUFACTURER") "Susumu Co Ltd")
        (field (name "VALUEDISPLAYED") "8.20k")
        (field (name "PUBLISHER") "Texas Instruments")
      )
      (libsource (lib "Altium Vault - TI") (part "Resistor"))
    )
    (comp (ref "R139")
      (value "RG1608P-103-B-T5")
      (footprint "0603")
      (description "RES, 10.0 k, 0.1%, 0.1 W, 0603")
      (fields
        (field (name "MANUFACTURER") "Susumu Co Ltd")
        (field (name "VALUEDISPLAYED") "10.0k")
        (field (name "PUBLISHER") "Texas Instruments")
      )
      (libsource (lib "Altium Vault - TI") (part "Resistor"))
    )
    (comp (ref "R140")
      (value "CRF1206-FZ-R002ELF")
      (footprint "1206")
      (description "RES, 0.002, 1%, 1 W, AEC-Q200 Grade 0, 1206")
      (fields (field (name "MANUFACTURER") "Bourns") (field (name "VALUEDISPLAYED") "0.002"))
      (libsource (lib "Altium Vault - TI") (part "Resistor"))
    )
    (comp (ref "R141")
      (value "RT0603BRD0710RL")
      (footprint "0603")
      (description "RES, 10.0, 0.1%, 0.1 W, 0603")
      (fields
        (field (name "MANUFACTURER") "Yageo America")
        (field (name "TOLERANCE_%") "0.1%")
        (field (name "VALUEDISPLAYED") "10.0")
        (field (name "PUBLISHER") "Texas Instruments")
      )
      (libsource (lib "Altium Vault - TI") (part "Resistor"))
    )
    (comp (ref "R142")
      (value "RT0603BRD0710RL")
      (footprint "0603")
      (description "RES, 10.0, 0.1%, 0.1 W, 0603")
      (fields
        (field (name "MANUFACTURER") "Yageo America")
        (field (name "TOLERANCE_%") "0.1%")
        (field (name "VALUEDISPLAYED") "10.0")
        (field (name "PUBLISHER") "Texas Instruments")
      )
      (libsource (lib "Altium Vault - TI") (part "Resistor"))
    )
    (comp (ref "R143")
      (value "RT0603BRD0710RL")
      (footprint "0603")
      (description "RES, 10.0, 0.1%, 0.1 W, 0603")
      (fields
        (field (name "MANUFACTURER") "Yageo America")
        (field (name "TOLERANCE_%") "0.1%")
        (field (name "VALUEDISPLAYED") "10.0")
        (field (name "PUBLISHER") "Texas Instruments")
      )
      (libsource (lib "Altium Vault - TI") (part "Resistor"))
    )
    (comp (ref "R144")
      (value "RT0603BRD0710RL")
      (footprint "0603")
      (description "RES, 10.0, 0.1%, 0.1 W, 0603")
      (fields
        (field (name "MANUFACTURER") "Yageo America")
        (field (name "TOLERANCE_%") "0.1%")
        (field (name "VALUEDISPLAYED") "10.0")
        (field (name "PUBLISHER") "Texas Instruments")
      )
      (libsource (lib "Altium Vault - TI") (part "Resistor"))
    )
    (comp (ref "R145")
      (value "CRCW060310K0FKEA")
      (footprint "0603")
      (description "RES, 10.0 k, 1%, 0.1 W, AEC-Q200 Grade 0, 0603")
      (fields (field (name "MANUFACTURER") "Vishay-Dale") (field (name "VALUEDISPLAYED") "10.0k"))
      (libsource (lib "Altium Vault - TI") (part "Resistor"))
    )
    (comp (ref "R146")
      (value "PTCEL13R600LBE")
      (footprint "FP-PTCEL13R600LBE_RADIAL-MFG")
      (description "PTCEL Series 500 V 60 Ohm ±30 % Radial Inrush Current Limiter PTC Thermistor")
      (fields
        (field (name "DIGIKEY PART NUMBER") "BC3317-ND")
        (field (name "MANUFACTURER") "Vishay Bccomponents")
      )
      (libsource (lib "Altium Vault - TI") (part "SYM-PTCEL13R600LBE"))
    )
    (comp (ref "R147")
      (value "CRCW060310K0FKEA")
      (footprint "0603")
      (description "RES, 10.0 k, 1%, 0.1 W, AEC-Q200 Grade 0, 0603")
      (fields (field (name "MANUFACTURER") "Vishay-Dale") (field (name "VALUEDISPLAYED") "10.0k"))
      (libsource (lib "Altium Vault - TI") (part "Resistor"))
    )
    (comp (ref "R148")
      (value "RC0603FR-0756RL")
      (footprint "0603")
      (description "RES, 56.0, 1%, 0.1 W, 0603")
      (fields (field (name "MANUFACTURER") "Yageo") (field (name "VALUEDISPLAYED") "56.0"))
      (libsource (lib "Altium Vault - TI") (part "Resistor"))
    )
    (comp (ref "R149")
      (value "RC0603FR-0747KL")
      (footprint "0603")
      (description "RES, 47.0 k, 1%, 0.1 W, 0603")
      (fields (field (name "MANUFACTURER") "Yageo") (field (name "VALUEDISPLAYED") "47.0k"))
      (libsource (lib "Altium Vault - TI") (part "Resistor"))
    )
    (comp (ref "R150")
      (value "RC0603FR-0756RL")
      (footprint "0603")
      (description "RES, 56.0, 1%, 0.1 W, 0603")
      (fields (field (name "MANUFACTURER") "Yageo") (field (name "VALUEDISPLAYED") "56.0"))
      (libsource (lib "Altium Vault - TI") (part "Resistor"))
    )
    (comp (ref "R151")
      (value "RC0603FR-0756RL")
      (footprint "0603")
      (description "RES, 56.0, 1%, 0.1 W, 0603")
      (fields (field (name "MANUFACTURER") "Yageo") (field (name "VALUEDISPLAYED") "56.0"))
      (libsource (lib "Altium Vault - TI") (part "Resistor"))
    )
    (comp (ref "R152")
      (value "CRCW060310K0FKEA")
      (footprint "0603")
      (description "RES, 10.0 k, 1%, 0.1 W, AEC-Q200 Grade 0, 0603")
      (fields (field (name "MANUFACTURER") "Vishay-Dale") (field (name "VALUEDISPLAYED") "10.0k"))
      (libsource (lib "Altium Vault - TI") (part "Resistor"))
    )
    (comp (ref "R153")
      (value "CRCW060310K0FKEA")
      (footprint "0603")
      (description "RES, 10.0 k, 1%, 0.1 W, AEC-Q200 Grade 0, 0603")
      (fields (field (name "MANUFACTURER") "Vishay-Dale") (field (name "VALUEDISPLAYED") "10.0k"))
      (libsource (lib "Altium Vault - TI") (part "Resistor"))
    )
    (comp (ref "R154")
      (value "RC0603FR-0756RL")
      (footprint "0603")
      (description "RES, 56.0, 1%, 0.1 W, 0603")
      (fields (field (name "MANUFACTURER") "Yageo") (field (name "VALUEDISPLAYED") "56.0"))
      (libsource (lib "Altium Vault - TI") (part "Resistor"))
    )
    (comp (ref "R155")
      (value "RC0603FR-0756RL")
      (footprint "0603")
      (description "RES, 56.0, 1%, 0.1 W, 0603")
      (fields (field (name "MANUFACTURER") "Yageo") (field (name "VALUEDISPLAYED") "56.0"))
      (libsource (lib "Altium Vault - TI") (part "Resistor"))
    )
    (comp (ref "R156")
      (value "RC0603FR-0756RL")
      (footprint "0603")
      (description "RES, 56.0, 1%, 0.1 W, 0603")
      (fields (field (name "MANUFACTURER") "Yageo") (field (name "VALUEDISPLAYED") "56.0"))
      (libsource (lib "Altium Vault - TI") (part "Resistor"))
    )
    (comp (ref "R157")
      (value "CRCW060310K0FKEA")
      (footprint "0603")
      (description "RES, 10.0 k, 1%, 0.1 W, AEC-Q200 Grade 0, 0603")
      (fields (field (name "MANUFACTURER") "Vishay-Dale") (field (name "VALUEDISPLAYED") "10.0k"))
      (libsource (lib "Altium Vault - TI") (part "Resistor"))
    )
    (comp (ref "R158")
      (value "RC0603FR-0756RL")
      (footprint "0603")
      (description "RES, 56.0, 1%, 0.1 W, 0603")
      (fields (field (name "MANUFACTURER") "Yageo") (field (name "VALUEDISPLAYED") "56.0"))
      (libsource (lib "Altium Vault - TI") (part "Resistor"))
    )
    (comp (ref "R159")
      (value "RC0603FR-0756RL")
      (footprint "0603")
      (description "RES, 56.0, 1%, 0.1 W, 0603")
      (fields (field (name "MANUFACTURER") "Yageo") (field (name "VALUEDISPLAYED") "56.0"))
      (libsource (lib "Altium Vault - TI") (part "Resistor"))
    )
    (comp (ref "R160")
      (value "RC0603FR-0756RL")
      (footprint "0603")
      (description "RES, 56.0, 1%, 0.1 W, 0603")
      (fields (field (name "MANUFACTURER") "Yageo") (field (name "VALUEDISPLAYED") "56.0"))
      (libsource (lib "Altium Vault - TI") (part "Resistor"))
    )
    (comp (ref "R161")
      (value "RC0603FR-0756RL")
      (footprint "0603")
      (description "RES, 56.0, 1%, 0.1 W, 0603")
      (fields (field (name "MANUFACTURER") "Yageo") (field (name "VALUEDISPLAYED") "56.0"))
      (libsource (lib "Altium Vault - TI") (part "Resistor"))
    )
    (comp (ref "R162")
      (value "RC0603FR-0756RL")
      (footprint "0603")
      (description "RES, 56.0, 1%, 0.1 W, 0603")
      (fields (field (name "MANUFACTURER") "Yageo") (field (name "VALUEDISPLAYED") "56.0"))
      (libsource (lib "Altium Vault - TI") (part "Resistor"))
    )
    (comp (ref "R163")
      (value "RC0603FR-0756RL")
      (footprint "0603")
      (description "RES, 56.0, 1%, 0.1 W, 0603")
      (fields (field (name "MANUFACTURER") "Yageo") (field (name "VALUEDISPLAYED") "56.0"))
      (libsource (lib "Altium Vault - TI") (part "Resistor"))
    )
    (comp (ref "R164")
      (value "RC0603FR-0756RL")
      (footprint "0603")
      (description "RES, 56.0, 1%, 0.1 W, 0603")
      (fields (field (name "MANUFACTURER") "Yageo") (field (name "VALUEDISPLAYED") "56.0"))
      (libsource (lib "Altium Vault - TI") (part "Resistor"))
    )
    (comp (ref "R165")
      (value "RC0603FR-0756RL")
      (footprint "0603")
      (description "RES, 56.0, 1%, 0.1 W, 0603")
      (fields (field (name "MANUFACTURER") "Yageo") (field (name "VALUEDISPLAYED") "56.0"))
      (libsource (lib "Altium Vault - TI") (part "Resistor"))
    )
    (comp (ref "R166")
      (value "RC0603FR-0756RL")
      (footprint "0603")
      (description "RES, 56.0, 1%, 0.1 W, 0603")
      (fields (field (name "MANUFACTURER") "Yageo") (field (name "VALUEDISPLAYED") "56.0"))
      (libsource (lib "Altium Vault - TI") (part "Resistor"))
    )
    (comp (ref "R167")
      (value "RC0603FR-0756RL")
      (footprint "0603")
      (description "RES, 56.0, 1%, 0.1 W, 0603")
      (fields (field (name "MANUFACTURER") "Yageo") (field (name "VALUEDISPLAYED") "56.0"))
      (libsource (lib "Altium Vault - TI") (part "Resistor"))
    )
    (comp (ref "R168")
      (value "RC0603FR-0756RL")
      (footprint "0603")
      (description "RES, 56.0, 1%, 0.1 W, 0603")
      (fields (field (name "MANUFACTURER") "Yageo") (field (name "VALUEDISPLAYED") "56.0"))
      (libsource (lib "Altium Vault - TI") (part "Resistor"))
    )
    (comp (ref "R169")
      (value "RC0603FR-0756RL")
      (footprint "0603")
      (description "RES, 56.0, 1%, 0.1 W, 0603")
      (fields (field (name "MANUFACTURER") "Yageo") (field (name "VALUEDISPLAYED") "56.0"))
      (libsource (lib "Altium Vault - TI") (part "Resistor"))
    )
    (comp (ref "R170")
      (value "RC0603FR-0756RL")
      (footprint "0603")
      (description "RES, 56.0, 1%, 0.1 W, 0603")
      (fields (field (name "MANUFACTURER") "Yageo") (field (name "VALUEDISPLAYED") "56.0"))
      (libsource (lib "Altium Vault - TI") (part "Resistor"))
    )
    (comp (ref "R171")
      (value "RC0603FR-0756RL")
      (footprint "0603")
      (description "RES, 56.0, 1%, 0.1 W, 0603")
      (fields (field (name "MANUFACTURER") "Yageo") (field (name "VALUEDISPLAYED") "56.0"))
      (libsource (lib "Altium Vault - TI") (part "Resistor"))
    )
    (comp (ref "R172")
      (value "RC0603FR-0756RL")
      (footprint "0603")
      (description "RES, 56.0, 1%, 0.1 W, 0603")
      (fields (field (name "MANUFACTURER") "Yageo") (field (name "VALUEDISPLAYED") "56.0"))
      (libsource (lib "Altium Vault - TI") (part "Resistor"))
    )
    (comp (ref "R173")
      (value "RC0603FR-0756RL")
      (footprint "0603")
      (description "RES, 56.0, 1%, 0.1 W, 0603")
      (fields (field (name "MANUFACTURER") "Yageo") (field (name "VALUEDISPLAYED") "56.0"))
      (libsource (lib "Altium Vault - TI") (part "Resistor"))
    )
    (comp (ref "R174")
      (value "RC0603FR-0756RL")
      (footprint "0603")
      (description "RES, 56.0, 1%, 0.1 W, 0603")
      (fields (field (name "MANUFACTURER") "Yageo") (field (name "VALUEDISPLAYED") "56.0"))
      (libsource (lib "Altium Vault - TI") (part "Resistor"))
    )
    (comp (ref "R175")
      (value "CRCW060310K0FKEA")
      (footprint "0603")
      (description "RES, 10.0 k, 1%, 0.1 W, AEC-Q200 Grade 0, 0603")
      (fields (field (name "MANUFACTURER") "Vishay-Dale") (field (name "VALUEDISPLAYED") "10.0k"))
      (libsource (lib "Altium Vault - TI") (part "Resistor"))
    )
    (comp (ref "R176")
      (value "CRCW060310K0FKEA")
      (footprint "0603")
      (description "RES, 10.0 k, 1%, 0.1 W, AEC-Q200 Grade 0, 0603")
      (fields (field (name "MANUFACTURER") "Vishay-Dale") (field (name "VALUEDISPLAYED") "10.0k"))
      (libsource (lib "Altium Vault - TI") (part "Resistor"))
    )
    (comp (ref "R177")
      (value "CRCW060310K0FKEA")
      (footprint "0603")
      (description "RES, 10.0 k, 1%, 0.1 W, AEC-Q200 Grade 0, 0603")
      (fields (field (name "MANUFACTURER") "Vishay-Dale") (field (name "VALUEDISPLAYED") "10.0k"))
      (libsource (lib "Altium Vault - TI") (part "Resistor"))
    )
    (comp (ref "R178")
      (value "CRCW060310K0FKEA")
      (footprint "0603")
      (description "RES, 10.0 k, 1%, 0.1 W, AEC-Q200 Grade 0, 0603")
      (fields (field (name "MANUFACTURER") "Vishay-Dale") (field (name "VALUEDISPLAYED") "10.0k"))
      (libsource (lib "Altium Vault - TI") (part "Resistor"))
    )
    (comp (ref "R179")
      (value "CRCW060310K0FKEA")
      (footprint "0603")
      (description "RES, 10.0 k, 1%, 0.1 W, AEC-Q200 Grade 0, 0603")
      (fields (field (name "MANUFACTURER") "Vishay-Dale") (field (name "VALUEDISPLAYED") "10.0k"))
      (libsource (lib "Altium Vault - TI") (part "Resistor"))
    )
    (comp (ref "R180")
      (value "RC0603FR-0756RL")
      (footprint "0603")
      (description "RES, 56.0, 1%, 0.1 W, 0603")
      (fields (field (name "MANUFACTURER") "Yageo") (field (name "VALUEDISPLAYED") "56.0"))
      (libsource (lib "Altium Vault - TI") (part "Resistor"))
    )
    (comp (ref "R181")
      (value "RC0603FR-0756RL")
      (footprint "0603")
      (description "RES, 56.0, 1%, 0.1 W, 0603")
      (fields (field (name "MANUFACTURER") "Yageo") (field (name "VALUEDISPLAYED") "56.0"))
      (libsource (lib "Altium Vault - TI") (part "Resistor"))
    )
    (comp (ref "R182")
      (value "RC0603FR-0756RL")
      (footprint "0603")
      (description "RES, 56.0, 1%, 0.1 W, 0603")
      (fields (field (name "MANUFACTURER") "Yageo") (field (name "VALUEDISPLAYED") "56.0"))
      (libsource (lib "Altium Vault - TI") (part "Resistor"))
    )
    (comp (ref "TP31")
      (value "5001")
      (footprint "Keystone5001")
      (description "Test Point, Miniature, Black, TH")
      (fields
        (field (name "MANUFACTURER") "Keystone Electronics")
        (field (name "PUBLISHER") "Texas Instruments")
      )
      (libsource (lib "Altium Vault - TI") (part "5001"))
    )
    (comp (ref "TP32")
      (value "5001")
      (footprint "Keystone5001")
      (description "Test Point, Miniature, Black, TH")
      (fields
        (field (name "MANUFACTURER") "Keystone Electronics")
        (field (name "PUBLISHER") "Texas Instruments")
      )
      (libsource (lib "Altium Vault - TI") (part "5001"))
    )
    (comp (ref "TP33")
      (value "5001")
      (footprint "Keystone5001")
      (description "Test Point, Miniature, Black, TH")
      (fields
        (field (name "MANUFACTURER") "Keystone Electronics")
        (field (name "PUBLISHER") "Texas Instruments")
      )
      (libsource (lib "Altium Vault - TI") (part "5001"))
    )
    (comp (ref "TP34")
      (value "5001")
      (footprint "Keystone5001")
      (description "Test Point, Miniature, Black, TH")
      (fields
        (field (name "MANUFACTURER") "Keystone Electronics")
        (field (name "PUBLISHER") "Texas Instruments")
      )
      (libsource (lib "Altium Vault - TI") (part "5001"))
    )
    (comp (ref "TP35")
      (value "5001")
      (footprint "Keystone5001")
      (description "Test Point, Miniature, Black, TH")
      (fields
        (field (name "MANUFACTURER") "Keystone Electronics")
        (field (name "PUBLISHER") "Texas Instruments")
      )
      (libsource (lib "Altium Vault - TI") (part "5001"))
    )
    (comp (ref "TP36")
      (value "5001")
      (footprint "Keystone5001")
      (description "Test Point, Miniature, Black, TH")
      (fields
        (field (name "MANUFACTURER") "Keystone Electronics")
        (field (name "PUBLISHER") "Texas Instruments")
      )
      (libsource (lib "Altium Vault - TI") (part "5001"))
    )
    (comp (ref "TP37")
      (value "5001")
      (footprint "Keystone5001")
      (description "Test Point, Miniature, Black, TH")
      (fields
        (field (name "MANUFACTURER") "Keystone Electronics")
        (field (name "PUBLISHER") "Texas Instruments")
      )
      (libsource (lib "Altium Vault - TI") (part "5001"))
    )
    (comp (ref "TP38")
      (value "5002")
      (footprint "Keystone5002")
      (description "Test Point, Miniature, White, TH")
      (fields
        (field (name "MANUFACTURER") "Keystone Electronics")
        (field (name "PUBLISHER") "Texas Instruments")
      )
      (libsource (lib "Altium Vault - TI") (part "5002"))
    )
    (comp (ref "TP39")
      (value "5001")
      (footprint "Keystone5001")
      (description "Test Point, Miniature, Black, TH")
      (fields
        (field (name "MANUFACTURER") "Keystone Electronics")
        (field (name "PUBLISHER") "Texas Instruments")
      )
      (libsource (lib "Altium Vault - TI") (part "5001"))
    )
    (comp (ref "TP40")
      (value "5001")
      (footprint "Keystone5001")
      (description "Test Point, Miniature, Black, TH")
      (fields
        (field (name "MANUFACTURER") "Keystone Electronics")
        (field (name "PUBLISHER") "Texas Instruments")
      )
      (libsource (lib "Altium Vault - TI") (part "5001"))
    )
    (comp (ref "TP41")
      (value "5004")
      (footprint "Keystone5004")
      (description "Test Point, Miniature, Yellow, TH")
      (fields
        (field (name "MANUFACTURER") "Keystone Electronics")
        (field (name "PUBLISHER") "Texas Instruments")
      )
      (libsource (lib "Altium Vault - TI") (part "5004"))
    )
    (comp (ref "TP42")
      (value "5003")
      (footprint "Keystone5003")
      (description "Test Point, Miniature, Orange, TH")
      (fields
        (field (name "MANUFACTURER") "Keystone Electronics")
        (field (name "PUBLISHER") "Texas Instruments")
      )
      (libsource (lib "Altium Vault - TI") (part "5003"))
    )
    (comp (ref "TP43")
      (value "5001")
      (footprint "Keystone5001")
      (description "Test Point, Miniature, Black, TH")
      (fields
        (field (name "MANUFACTURER") "Keystone Electronics")
        (field (name "PUBLISHER") "Texas Instruments")
      )
      (libsource (lib "Altium Vault - TI") (part "5001"))
    )
    (comp (ref "TP44")
      (value "5001")
      (footprint "Keystone5001")
      (description "Test Point, Miniature, Black, TH")
      (fields
        (field (name "MANUFACTURER") "Keystone Electronics")
        (field (name "PUBLISHER") "Texas Instruments")
      )
      (libsource (lib "Altium Vault - TI") (part "5001"))
    )
    (comp (ref "TP45")
      (value "S2751-46R")
      (footprint "Harwin_S2751-46R")
      (description "Test Point, SMT")
      (fields (field (name "MANUFACTURER") "Harwin") (field (name "PUBLISHER") "Texas Instruments"))
      (libsource (lib "Altium Vault - TI") (part "TESTPOINT"))
    )
    (comp (ref "TP46")
      (value "S2751-46R")
      (footprint "Harwin_S2751-46R")
      (description "Test Point, SMT")
      (fields (field (name "MANUFACTURER") "Harwin") (field (name "PUBLISHER") "Texas Instruments"))
      (libsource (lib "Altium Vault - TI") (part "TESTPOINT"))
    )
    (comp (ref "TP47")
      (value "S2751-46R")
      (footprint "Harwin_S2751-46R")
      (description "Test Point, SMT")
      (fields (field (name "MANUFACTURER") "Harwin") (field (name "PUBLISHER") "Texas Instruments"))
      (libsource (lib "Altium Vault - TI") (part "TESTPOINT"))
    )
    (comp (ref "TP56")
      (value "5000")
      (footprint "Keystone5000")
      (description "Test Point, Miniature, Red, TH")
      (fields
        (field (name "MANUFACTURER") "Keystone Electronics")
        (field (name "PUBLISHER") "Texas Instruments")
      )
      (libsource (lib "Altium Vault - TI") (part "5000"))
    )
    (comp (ref "TP57")
      (value "5001")
      (footprint "Keystone5001")
      (description "Test Point, Miniature, Black, TH")
      (fields
        (field (name "MANUFACTURER") "Keystone Electronics")
        (field (name "PUBLISHER") "Texas Instruments")
      )
      (libsource (lib "Altium Vault - TI") (part "5001"))
    )
    (comp (ref "TP58")
      (value "5001")
      (footprint "Keystone5001")
      (description "Test Point, Miniature, Black, TH")
      (fields
        (field (name "MANUFACTURER") "Keystone Electronics")
        (field (name "PUBLISHER") "Texas Instruments")
      )
      (libsource (lib "Altium Vault - TI") (part "5001"))
    )
    (comp (ref "TP59")
      (value "5001")
      (footprint "Keystone5001")
      (description "Test Point, Miniature, Black, TH")
      (fields
        (field (name "MANUFACTURER") "Keystone Electronics")
        (field (name "PUBLISHER") "Texas Instruments")
      )
      (libsource (lib "Altium Vault - TI") (part "5001"))
    )
    (comp (ref "TP60")
      (value "5001")
      (footprint "Keystone5001")
      (description "Test Point, Miniature, Black, TH")
      (fields
        (field (name "MANUFACTURER") "Keystone Electronics")
        (field (name "PUBLISHER") "Texas Instruments")
      )
      (libsource (lib "Altium Vault - TI") (part "5001"))
    )
    (comp (ref "TP61")
      (value "5001")
      (footprint "Keystone5001")
      (description "Test Point, Miniature, Black, TH")
      (fields
        (field (name "MANUFACTURER") "Keystone Electronics")
        (field (name "PUBLISHER") "Texas Instruments")
      )
      (libsource (lib "Altium Vault - TI") (part "5001"))
    )
    (comp (ref "TP62")
      (value "5001")
      (footprint "Keystone5001")
      (description "Test Point, Miniature, Black, TH")
      (fields
        (field (name "MANUFACTURER") "Keystone Electronics")
        (field (name "PUBLISHER") "Texas Instruments")
      )
      (libsource (lib "Altium Vault - TI") (part "5001"))
    )
    (comp (ref "TP64")
      (value "5001")
      (footprint "Keystone5001")
      (description "Test Point, Miniature, Black, TH")
      (fields
        (field (name "MANUFACTURER") "Keystone Electronics")
        (field (name "PUBLISHER") "Texas Instruments")
      )
      (libsource (lib "Altium Vault - TI") (part "5001"))
    )
    (comp (ref "TP65")
      (value "5001")
      (footprint "Keystone5001")
      (description "Test Point, Miniature, Black, TH")
      (fields
        (field (name "MANUFACTURER") "Keystone Electronics")
        (field (name "PUBLISHER") "Texas Instruments")
      )
      (libsource (lib "Altium Vault - TI") (part "5001"))
    )
    (comp (ref "TP66")
      (value "5001")
      (footprint "Keystone5001")
      (description "Test Point, Miniature, Black, TH")
      (fields
        (field (name "MANUFACTURER") "Keystone Electronics")
        (field (name "PUBLISHER") "Texas Instruments")
      )
      (libsource (lib "Altium Vault - TI") (part "5001"))
    )
    (comp (ref "TP67")
      (value "5001")
      (footprint "Keystone5001")
      (description "Test Point, Miniature, Black, TH")
      (fields
        (field (name "MANUFACTURER") "Keystone Electronics")
        (field (name "PUBLISHER") "Texas Instruments")
      )
      (libsource (lib "Altium Vault - TI") (part "5001"))
    )
    (comp (ref "TP68")
      (value "5001")
      (footprint "Keystone5001")
      (description "Test Point, Miniature, Black, TH")
      (fields
        (field (name "MANUFACTURER") "Keystone Electronics")
        (field (name "PUBLISHER") "Texas Instruments")
      )
      (libsource (lib "Altium Vault - TI") (part "5001"))
    )
    (comp (ref "TP69")
      (value "5001")
      (footprint "Keystone5001")
      (description "Test Point, Miniature, Black, TH")
      (fields
        (field (name "MANUFACTURER") "Keystone Electronics")
        (field (name "PUBLISHER") "Texas Instruments")
      )
      (libsource (lib "Altium Vault - TI") (part "5001"))
    )
    (comp (ref "TP73")
      (value "S2751-46R")
      (footprint "Harwin_S2751-46R")
      (description "Test Point, SMT")
      (fields (field (name "MANUFACTURER") "Harwin") (field (name "PUBLISHER") "Texas Instruments"))
      (libsource (lib "Altium Vault - TI") (part "TESTPOINT"))
    )
    (comp (ref "TP74")
      (value "S2751-46R")
      (footprint "Harwin_S2751-46R")
      (description "Test Point, SMT")
      (fields (field (name "MANUFACTURER") "Harwin") (field (name "PUBLISHER") "Texas Instruments"))
      (libsource (lib "Altium Vault - TI") (part "TESTPOINT"))
    )
    (comp (ref "U28")
      (value "AMC3330QDWERQ1")
      (footprint "DWE0016A-MFG")
      (description "Precision, ±1-V Input, Reinforced Isolated Amplifier With Integrated DC/DC Converter")
      (fields (field (name "MANUFACTURER") "Texas Instruments") (field (name "PARTNUMBER") "AMC3330QDWERQ1"))
      (libsource (lib "Altium Vault - TI") (part "SYM-AMC3330QDWERQ1"))
    )
    (comp (ref "U29")
      (value "AMC1302DWV")
      (footprint "DWV0008A")
      (description "Precision Reinforced Isolated Amplifier for Current Sensing, DWV0008A (SOIC-8)")
      (fields
        (field (name "ALTERNATE PARTNUMBER") "AMC1302DWVR")
        (field (name "MANUFACTURER") "Texas Instruments")
        (field (name "PARTNUMBER") "AMC1302DWV")
      )
      (libsource (lib "Altium Vault - TI") (part "AMC1301"))
    )
    (comp (ref "U30")
      (value "AMC1311BDWVR")
      (footprint "DWV0008A")
      (description "Precision, 2-V Input, Reinforced Isolated Amplifier, DWV0008A (SOIC-8)")
      (fields
        (field (name "ALTERNATE PARTNUMBER") "AMC1311BDWV")
        (field (name "MANUFACTURER") "Texas Instruments")
        (field (name "PARTNUMBER") "AMC1311BDWVR")
      )
      (libsource (lib "Altium Vault - TI") (part "AMC1311"))
    )
    (comp (ref "U31")
      (value "AMC1302DWV")
      (footprint "DWV0008A")
      (description "Precision Reinforced Isolated Amplifier for Current Sensing, DWV0008A (SOIC-8)")
      (fields
        (field (name "ALTERNATE PARTNUMBER") "AMC1302DWVR")
        (field (name "MANUFACTURER") "Texas Instruments")
        (field (name "PARTNUMBER") "AMC1302DWV")
      )
      (libsource (lib "Altium Vault - TI") (part "AMC1301"))
    )
    (comp (ref "U32")
      (value "TMCS1123B4QDVGR")
      (footprint "DVG0010A-MFG")
      (fields (field (name "MANUFACTURER") "Texas Instruments") (field (name "PARTNUMBER") "TMCS1123B4QDVGR"))
      (libsource (lib "Altium Vault - TI") (part "SYM-TMCS1123B4QDVGR"))
    )
    (comp (ref "U33")
      (value "SN74LVC1G08MDBVREP")
      (footprint "DBV0005A_N")
      (description "Enhanced Product Single 2-Input Positive-And Gate, DBV0005A, LARGE T&R")
      (fields
        (field (name "GENERIC PART NUMBER") "SN74LVC1G08-EP")
        (field (name "MANUFACTURER") "Texas Instruments")
        (field (name "PARTNUMBER") "SN74LVC1G08MDBVREP")
      )
      (libsource (lib "Altium Vault - TI") (part "TI-SN74XXX1X08-5"))
    )
    (comp (ref "U34")
      (value "SN74LVC1G08MDBVREP")
      (footprint "DBV0005A_N")
      (description "Enhanced Product Single 2-Input Positive-And Gate, DBV0005A, LARGE T&R")
      (fields
        (field (name "GENERIC PART NUMBER") "SN74LVC1G08-EP")
        (field (name "MANUFACTURER") "Texas Instruments")
        (field (name "PARTNUMBER") "SN74LVC1G08MDBVREP")
      )
      (libsource (lib "Altium Vault - TI") (part "TI-SN74XXX1X08-5"))
    )
    (comp (ref "U35")
      (value "SN74LVC1G14DBVT")
      (footprint "DBV0005A_N")
      (description "Single Schmitt-Trigger Inverter, DBV0005A, SMALL T&R")
      (fields
        (field (name "GENERIC PART NUMBER") "SN74LVC1G14")
        (field (name "MANUFACTURER") "Texas Instruments")
        (field (name "PARTNUMBER") "SN74LVC1G14DBVT")
      )
      (libsource (lib "Altium Vault - TI") (part "TI-SN74XXX1XX4-XX-5-SCHMITT"))
    )
    (comp (ref "ZZ1")
      (value "These assemblies are ESD sensitive, ESD precautions shall be observed.")
      (footprint "AssemblyNote")
      (fields (field (name "PUBLISHER") "Texas Instruments"))
      (libsource (lib "Altium Vault - TI") (part "Assembly Note"))
    )
    (comp (ref "ZZ2")
      (value "These assemblies must be clean and free from flux and all contaminants. Use of no clean flux is not acceptable.")
      (footprint "AssemblyNote")
      (fields (field (name "PUBLISHER") "Texas Instruments"))
      (libsource (lib "Altium Vault - TI") (part "Assembly Note"))
    )
    (comp (ref "ZZ3")
      (value "These assemblies must comply with workmanship standards IPC-A-610 Class 2, unless otherwise specified.")
      (footprint "AssemblyNote")
      (fields (field (name "PUBLISHER") "Texas Instruments"))
      (libsource (lib "Altium Vault - TI") (part "Assembly Note"))
    )
  )
  (nets
    (net (code "1") (name "/DCAC_~{ENABLE}") (class "Default")
      (node (ref "R182") (pin "1") (pinfunction "1_1") (pintype "passive"))
    )
    (net (code "2") (name "/DCLINK+_HV") (class "Default")
      (node (ref "C171") (pin "2") (pinfunction "2_2") (pintype "passive"))
      (node (ref "C172") (pin "2") (pinfunction "2_2") (pintype "passive"))
      (node (ref "C173") (pin "2") (pinfunction "ANODE_2") (pintype "passive"))
      (node (ref "C174") (pin "1") (pinfunction "1_1") (pintype "passive"))
      (node (ref "C175") (pin "2") (pinfunction "ANODE_2") (pintype "passive"))
      (node (ref "C178") (pin "1") (pinfunction "1_1") (pintype "passive"))
      (node (ref "C179") (pin "2") (pinfunction "ANODE_2") (pintype "passive"))
      (node (ref "C180") (pin "1") (pinfunction "1_1") (pintype "passive"))
      (node (ref "C181") (pin "1") (pinfunction "1_1") (pintype "passive"))
      (node (ref "J16") (pin "1") (pinfunction "1_1") (pintype "passive"))
      (node (ref "R120") (pin "2") (pinfunction "2_2") (pintype "passive"))
      (node (ref "TP31") (pin "1") (pintype "passive"))
      (node (ref "TP32") (pin "1") (pintype "passive"))
      (node (ref "TP33") (pin "1") (pintype "passive"))
      (node (ref "TP34") (pin "1") (pintype "passive"))
      (node (ref "TP56") (pin "1") (pintype "passive"))
      (node (ref "TP61") (pin "1") (pintype "passive"))
      (node (ref "TP62") (pin "1") (pintype "passive"))
    )
    (net (code "3") (name "/I_AC_H") (class "Default")
      (node (ref "R150") (pin "1") (pinfunction "1_1") (pintype "passive"))
      (node (ref "R162") (pin "1") (pinfunction "1_1") (pintype "passive"))
    )
    (net (code "4") (name "/I_AC_L") (class "Default")
      (node (ref "R148") (pin "1") (pinfunction "1_1") (pintype "passive"))
      (node (ref "R161") (pin "1") (pinfunction "1_1") (pintype "passive"))
    )
    (net (code "5") (name "/I_DC_H") (class "Default")
      (node (ref "R158") (pin "1") (pinfunction "1_1") (pintype "passive"))
    )
    (net (code "6") (name "/I_DC_L") (class "Default")
      (node (ref "R155") (pin "1") (pinfunction "1_1") (pintype "passive"))
    )
    (net (code "7") (name "/PFC_FAULT") (class "Default")
      (node (ref "C216") (pin "1") (pinfunction "1_1") (pintype "passive"))
      (node (ref "R180") (pin "2") (pinfunction "2_2") (pintype "passive"))
    )
    (net (code "8") (name "/PFC_H_PWM") (class "Default")
      (node (ref "R165") (pin "2") (pinfunction "2_2") (pintype "passive"))
    )
    (net (code "9") (name "/PFC_H_TEMP") (class "Default")
      (node (ref "C221") (pin "2") (pinfunction "2_2") (pintype "passive"))
      (node (ref "R171") (pin "2") (pinfunction "2_2") (pintype "passive"))
    )
    (net (code "10") (name "/PFC_L_PWM") (class "Default")
      (node (ref "R163") (pin "2") (pinfunction "2_2") (pintype "passive"))
    )
    (net (code "11") (name "/PFC_L_TEMP") (class "Default")
      (node (ref "C220") (pin "1") (pinfunction "1_1") (pintype "passive"))
      (node (ref "R167") (pin "2") (pinfunction "2_2") (pintype "passive"))
    )
    (net (code "12") (name "/PFC_OC") (class "Default")
      (node (ref "C217") (pin "1") (pinfunction "1_1") (pintype "passive"))
      (node (ref "R174") (pin "2") (pinfunction "2_2") (pintype "passive"))
    )
    (net (code "13") (name "/PFC_RECT_H_PWM") (class "Default")
      (node (ref "R164") (pin "1") (pinfunction "1_1") (pintype "passive"))
    )
    (net (code "14") (name "/PFC_RECT_L_PWM") (class "Default")
      (node (ref "R166") (pin "1") (pinfunction "1_1") (pintype "passive"))
    )
    (net (code "15") (name "/PWM_HS_GaN") (class "Default")
      (node (ref "R165") (pin "1") (pinfunction "1_1") (pintype "passive"))
      (node (ref "TP68") (pin "1") (pintype "passive"))
    )
    (net (code "16") (name "/PWM_HS_Si") (class "Default")
      (node (ref "R164") (pin "2") (pinfunction "2_2") (pintype "passive"))
      (node (ref "R170") (pin "2") (pinfunction "2_2") (pintype "passive"))
      (node (ref "TP67") (pin "1") (pintype "passive"))
    )
    (net (code "17") (name "/PWM_LS_GaN") (class "Default")
      (node (ref "R163") (pin "1") (pinfunction "1_1") (pintype "passive"))
      (node (ref "TP66") (pin "1") (pintype "passive"))
    )
    (net (code "18") (name "/PWM_LS_Si") (class "Default")
      (node (ref "C208") (pin "1") (pinfunction "1_1") (pintype "passive"))
      (node (ref "R166") (pin "2") (pinfunction "2_2") (pintype "passive"))
      (node (ref "R175") (pin "2") (pinfunction "2_2") (pintype "passive"))
      (node (ref "TP69") (pin "1") (pintype "passive"))
      (node (ref "U35") (pin "2") (pinfunction "A_2") (pintype "input"))
    )
    (net (code "19") (name "/RELAY") (class "Default")
      (node (ref "R151") (pin "1") (pinfunction "1_1") (pintype "passive"))
      (node (ref "R181") (pin "2") (pinfunction "2_2") (pintype "passive"))
    )
    (net (code "20") (name "/RELAY_MCU") (class "Default")
      (node (ref "R181") (pin "1") (pinfunction "1_1") (pintype "passive"))
    )
    (net (code "21") (name "/SW_HF") (class "Default")
      (node (ref "L8") (pin "1") (pinfunction "1_1") (pintype "passive"))
    )
    (net (code "22") (name "/TEMP_HS_GaN") (class "Default")
      (node (ref "R171") (pin "1") (pinfunction "1_1") (pintype "passive"))
    )
    (net (code "23") (name "/TEMP_LS_GaN") (class "Default")
      (node (ref "R167") (pin "1") (pinfunction "1_1") (pintype "passive"))
    )
    (net (code "24") (name "/V_DC_H") (class "Default")
      (node (ref "R160") (pin "1") (pinfunction "1_1") (pintype "passive"))
    )
    (net (code "25") (name "/V_DC_L") (class "Default")
      (node (ref "R156") (pin "1") (pinfunction "1_1") (pintype "passive"))
    )
    (net (code "26") (name "/V_PCC_H") (class "Default")
      (node (ref "R154") (pin "2") (pinfunction "2_2") (pintype "passive"))
    )
    (net (code "27") (name "/V_PCC_L") (class "Default")
      (node (ref "R159") (pin "2") (pinfunction "2_2") (pintype "passive"))
    )
    (net (code "28") (name "/~{ENABL}E") (class "Default")
      (node (ref "R182") (pin "2") (pinfunction "2_2") (pintype "passive"))
    )
    (net (code "29") (name "/~{FAULT_GaN}") (class "Default")
      (node (ref "R180") (pin "1") (pinfunction "1_1") (pintype "passive"))
      (node (ref "U33") (pin "4") (pinfunction "Y_4") (pintype "output"))
    )
    (net (code "30") (name "/~{FAULT_HS_GaN}") (class "Default")
      (node (ref "R168") (pin "1") (pinfunction "1_1") (pintype "passive"))
    )
    (net (code "31") (name "/~{FAULT_LS_GaN}") (class "Default")
      (node (ref "R173") (pin "1") (pinfunction "1_1") (pintype "passive"))
    )
    (net (code "32") (name "/~{OC_GaN}") (class "Default")
      (node (ref "R174") (pin "1") (pinfunction "1_1") (pintype "passive"))
      (node (ref "U34") (pin "4") (pinfunction "Y_4") (pintype "output"))
    )
    (net (code "33") (name "/~{OC_HS_GaN}") (class "Default")
      (node (ref "R169") (pin "1") (pinfunction "1_1") (pintype "passive"))
    )
    (net (code "34") (name "/~{OC_LS_GaN}") (class "Default")
      (node (ref "R172") (pin "1") (pinfunction "1_1") (pintype "passive"))
    )
    (net (code "35") (name "3V3") (class "Default")
      (node (ref "C213") (pin "1") (pinfunction "1_1") (pintype "passive"))
      (node (ref "C214") (pin "1") (pinfunction "1_1") (pintype "passive"))
      (node (ref "FB9") (pin "2") (pinfunction "2_2") (pintype "passive"))
      (node (ref "R145") (pin "2") (pinfunction "2_2") (pintype "passive"))
      (node (ref "R152") (pin "2") (pinfunction "2_2") (pintype "passive"))
      (node (ref "R153") (pin "1") (pinfunction "1_1") (pintype "passive"))
      (node (ref "U33") (pin "5") (pinfunction "VCC_5") (pintype "power_in"))
      (node (ref "U34") (pin "5") (pinfunction "VCC_5") (pintype "power_in"))
    )
    (net (code "36") (name "5V") (class "Default")
      (node (ref "C206") (pin "1") (pinfunction "1_1") (pintype "passive"))
      (node (ref "C207") (pin "1") (pinfunction "+_1") (pintype "passive"))
      (node (ref "C215") (pin "1") (pinfunction "1_1") (pintype "passive"))
      (node (ref "D32") (pin "1") (pinfunction "K_1") (pintype "passive"))
      (node (ref "FB10") (pin "1") (pinfunction "1_1") (pintype "passive"))
      (node (ref "FB11") (pin "1") (pinfunction "1_1") (pintype "passive"))
      (node (ref "FB12") (pin "1") (pinfunction "1_1") (pintype "passive"))
      (node (ref "FB13") (pin "1") (pinfunction "1_1") (pintype "passive"))
      (node (ref "K1") (pin "A1") (pinfunction "A1_A1") (pintype "passive"))
      (node (ref "U35") (pin "5") (pinfunction "VCC_5") (pintype "power_in"))
    )
    (net (code "37") (name "5V_HS_Si") (class "Default")
      (node (ref "FB6") (pin "1") (pinfunction "1_1") (pintype "passive"))
    )
    (net (code "38") (name "5V_LS_CM") (class "Default")
      (node (ref "FB8") (pin "1") (pinfunction "1_1") (pintype "passive"))
      (node (ref "L11") (pin "3") (pinfunction "3_3") (pintype "passive"))
    )
    (net (code "39") (name "5V_LS_GaN") (class "Default")
      (node (ref "FB7") (pin "1") (pinfunction "1_1") (pintype "passive"))
      (node (ref "L11") (pin "4") (pinfunction "4_4") (pintype "passive"))
    )
    (net (code "40") (name "GND") (class "Default")
      (node (ref "C192") (pin "1") (pinfunction "1_1") (pintype "passive"))
      (node (ref "C194") (pin "1") (pinfunction "1_1") (pintype "passive"))
      (node (ref "C196") (pin "2") (pinfunction "2_2") (pintype "passive"))
      (node (ref "C197") (pin "2") (pinfunction "2_2") (pintype "passive"))
      (node (ref "C198") (pin "2") (pinfunction "2_2") (pintype "passive"))
      (node (ref "C199") (pin "2") (pinfunction "2_2") (pintype "passive"))
      (node (ref "C200") (pin "2") (pinfunction "2_2") (pintype "passive"))
      (node (ref "C201") (pin "2") (pinfunction "2_2") (pintype "passive"))
      (node (ref "C202") (pin "2") (pinfunction "2_2") (pintype "passive"))
      (node (ref "C203") (pin "2") (pinfunction "2_2") (pintype "passive"))
      (node (ref "C204") (pin "2") (pinfunction "2_2") (pintype "passive"))
      (node (ref "C205") (pin "2") (pinfunction "2_2") (pintype "passive"))
      (node (ref "C206") (pin "2") (pinfunction "2_2") (pintype "passive"))
      (node (ref "C207") (pin "2") (pinfunction "-_2") (pintype "passive"))
      (node (ref "C208") (pin "2") (pinfunction "2_2") (pintype "passive"))
      (node (ref "C209") (pin "2") (pinfunction "2_2") (pintype "passive"))
      (node (ref "C210") (pin "2") (pinfunction "2_2") (pintype "passive"))
      (node (ref "C211") (pin "2") (pinfunction "2_2") (pintype "passive"))
      (node (ref "C212") (pin "2") (pinfunction "2_2") (pintype "passive"))
      (node (ref "C213") (pin "2") (pinfunction "2_2") (pintype "passive"))
      (node (ref "C214") (pin "2") (pinfunction "2_2") (pintype "passive"))
      (node (ref "C215") (pin "2") (pinfunction "2_2") (pintype "passive"))
      (node (ref "C216") (pin "2") (pinfunction "2_2") (pintype "passive"))
      (node (ref "C217") (pin "2") (pinfunction "2_2") (pintype "passive"))
      (node (ref "C220") (pin "2") (pinfunction "2_2") (pintype "passive"))
      (node (ref "C221") (pin "1") (pinfunction "1_1") (pintype "passive"))
      (node (ref "Q5") (pin "3") (pinfunction "S_3") (pintype "passive"))
      (node (ref "R147") (pin "2") (pinfunction "2_2") (pintype "passive"))
      (node (ref "R157") (pin "1") (pinfunction "1_1") (pintype "passive"))
      (node (ref "R175") (pin "1") (pinfunction "1_1") (pintype "passive"))
      (node (ref "R176") (pin "1") (pinfunction "1_1") (pintype "passive"))
      (node (ref "R177") (pin "1") (pinfunction "1_1") (pintype "passive"))
      (node (ref "R178") (pin "1") (pinfunction "1_1") (pintype "passive"))
      (node (ref "R179") (pin "1") (pinfunction "1_1") (pintype "passive"))
      (node (ref "TP43") (pin "1") (pintype "passive"))
      (node (ref "TP44") (pin "1") (pintype "passive"))
      (node (ref "TP45") (pin "1") (pintype "passive"))
      (node (ref "TP46") (pin "1") (pintype "passive"))
      (node (ref "TP47") (pin "1") (pintype "passive"))
      (node (ref "U28") (pin "15") (pinfunction "DCDC_GND_15") (pintype "power_in"))
      (node (ref "U28") (pin "9") (pinfunction "GND_9") (pintype "power_in"))
      (node (ref "U29") (pin "5") (pinfunction "GND2_5") (pintype "power_in"))
      (node (ref "U30") (pin "5") (pinfunction "GND2_5") (pintype "power_in"))
      (node (ref "U31") (pin "5") (pinfunction "GND2_5") (pintype "power_in"))
      (node (ref "U32") (pin "3") (pinfunction "GND_3") (pintype "power_in"))
      (node (ref "U33") (pin "3") (pinfunction "GND_3") (pintype "power_in"))
      (node (ref "U34") (pin "3") (pinfunction "GND_3") (pintype "power_in"))
      (node (ref "U35") (pin "3") (pinfunction "GND_3") (pintype "power_in"))
    )
    (net (code "41") (name "GND_HS_Si") (class "Default")
      (node (ref "C191") (pin "1") (pinfunction "1_1") (pintype "passive"))
      (node (ref "R125") (pin "1") (pinfunction "1_1") (pintype "passive"))
      (node (ref "R141") (pin "1") (pinfunction "1_1") (pintype "passive"))
      (node (ref "TP73") (pin "1") (pintype "passive"))
      (node (ref "U31") (pin "4") (pinfunction "GND1_4") (pintype "power_in"))
    )
    (net (code "42") (name "GND_HV") (class "Default")
      (node (ref "R140") (pin "1") (pinfunction "1_1") (pintype "passive"))
      (node (ref "R143") (pin "1") (pinfunction "1_1") (pintype "passive"))
    )
    (net (code "43") (name "GND_LS_CM") (class "Default")
      (node (ref "C171") (pin "1") (pinfunction "1_1") (pintype "passive"))
      (node (ref "C172") (pin "1") (pinfunction "1_1") (pintype "passive"))
      (node (ref "C173") (pin "1") (pinfunction "CATHODE_1") (pintype "passive"))
      (node (ref "C174") (pin "2") (pinfunction "2_2") (pintype "passive"))
      (node (ref "C175") (pin "1") (pinfunction "CATHODE_1") (pintype "passive"))
      (node (ref "C178") (pin "2") (pinfunction "2_2") (pintype "passive"))
      (node (ref "C179") (pin "1") (pinfunction "CATHODE_1") (pintype "passive"))
      (node (ref "C180") (pin "2") (pinfunction "2_2") (pintype "passive"))
      (node (ref "C181") (pin "2") (pinfunction "2_2") (pintype "passive"))
      (node (ref "C182") (pin "2") (pinfunction "2_2") (pintype "passive"))
      (node (ref "C193") (pin "2") (pinfunction "2_2") (pintype "passive"))
      (node (ref "C195") (pin "2") (pinfunction "2_2") (pintype "passive"))
      (node (ref "J17") (pin "1") (pinfunction "1_1") (pintype "passive"))
      (node (ref "L11") (pin "1") (pinfunction "1_1") (pintype "passive"))
      (node (ref "L11") (pin "2") (pinfunction "2_2") (pintype "passive"))
      (node (ref "R138") (pin "1") (pinfunction "1_1") (pintype "passive"))
      (node (ref "R140") (pin "2") (pinfunction "2_2") (pintype "passive"))
      (node (ref "R144") (pin "1") (pinfunction "1_1") (pintype "passive"))
      (node (ref "TP36") (pin "1") (pintype "passive"))
      (node (ref "TP37") (pin "1") (pintype "passive"))
      (node (ref "TP39") (pin "1") (pintype "passive"))
      (node (ref "TP40") (pin "1") (pintype "passive"))
      (node (ref "TP57") (pin "1") (pintype "passive"))
      (node (ref "TP64") (pin "1") (pintype "passive"))
      (node (ref "TP65") (pin "1") (pintype "passive"))
      (node (ref "U29") (pin "4") (pinfunction "GND1_4") (pintype "power_in"))
      (node (ref "U30") (pin "3") (pinfunction "SHTDN_3") (pintype "input"))
      (node (ref "U30") (pin "4") (pinfunction "GND1_4") (pintype "power_in"))
    )
    (net (code "44") (name "GND_VM_HV") (class "Default")
      (node (ref "C184") (pin "1") (pinfunction "1_1") (pintype "passive"))
      (node (ref "C185") (pin "1") (pinfunction "1_1") (pintype "passive"))
      (node (ref "C186") (pin "1") (pinfunction "1_1") (pintype "passive"))
      (node (ref "C187") (pin "1") (pinfunction "1_1") (pintype "passive"))
      (node (ref "C188") (pin "1") (pinfunction "1_1") (pintype "passive"))
      (node (ref "C189") (pin "1") (pinfunction "1_1") (pintype "passive"))
      (node (ref "R136") (pin "1") (pinfunction "1_1") (pintype "passive"))
      (node (ref "R139") (pin "2") (pinfunction "2_2") (pintype "passive"))
      (node (ref "U28") (pin "2") (pinfunction "DCDC_HGND_2") (pintype "power_in"))
      (node (ref "U28") (pin "7") (pinfunction "INN_7") (pintype "input"))
      (node (ref "U28") (pin "8") (pinfunction "HGND_8") (pintype "power_in"))
    )
    (net (code "45") (name "GRID_GND") (class "Default")
      (node (ref "J18") (pin "1") (pinfunction "1_1") (pintype "passive"))
      (node (ref "J9") (pin "1") (pinfunction "1_1") (pintype "passive"))
      (node (ref "MP5") (pin "1") (pinfunction "1_1") (pintype "passive"))
      (node (ref "R118") (pin "2") (pinfunction "2_2") (pintype "passive"))
      (node (ref "R119") (pin "1") (pinfunction "1_1") (pintype "passive"))
      (node (ref "TP58") (pin "1") (pintype "passive"))
    )
    (net (code "46") (name "GRID_GND_1") (class "Default")
      (node (ref "C169") (pin "1") (pinfunction "1_1") (pintype "passive"))
      (node (ref "C170") (pin "2") (pinfunction "2_2") (pintype "passive"))
      (node (ref "MP9") (pin "1") (pinfunction "1_1") (pintype "passive"))
    )
    (net (code "47") (name "GRID_GND_2") (class "Default")
      (node (ref "C167") (pin "1") (pinfunction "1_1") (pintype "passive"))
      (node (ref "C168") (pin "2") (pinfunction "2_2") (pintype "passive"))
      (node (ref "MP10") (pin "1") (pinfunction "1_1") (pintype "passive"))
    )
    (net (code "48") (name "Net-(C167-Pad2)") (class "Default")
      (node (ref "C167") (pin "2") (pinfunction "2_2") (pintype "passive"))
      (node (ref "C176") (pin "2") (pinfunction "2_2") (pintype "passive"))
      (node (ref "K1") (pin "11") (pinfunction "11_11") (pintype "passive"))
      (node (ref "K1") (pin "6") (pinfunction "6_6") (pintype "passive"))
      (node (ref "R125") (pin "2") (pinfunction "2_2") (pintype "passive"))
      (node (ref "R142") (pin "1") (pinfunction "1_1") (pintype "passive"))
      (node (ref "R146") (pin "2") (pinfunction "2_2") (pintype "passive"))
      (node (ref "TP74") (pin "1") (pintype "passive"))
    )
    (net (code "49") (name "Net-(C168-Pad1)") (class "Default")
      (node (ref "C168") (pin "1") (pinfunction "1_1") (pintype "passive"))
      (node (ref "C176") (pin "1") (pinfunction "1_1") (pintype "passive"))
      (node (ref "L8") (pin "2") (pinfunction "2_2") (pintype "passive"))
      (node (ref "L9") (pin "4") (pinfunction "4_4") (pintype "passive"))
    )
    (net (code "50") (name "Net-(C169-Pad2)") (class "Default")
      (node (ref "C169") (pin "2") (pinfunction "2_2") (pintype "passive"))
      (node (ref "C177") (pin "2") (pinfunction "2_2") (pintype "passive"))
      (node (ref "L10") (pin "3") (pinfunction "3_3") (pintype "passive"))
      (node (ref "L9") (pin "2") (pinfunction "2_2") (pintype "passive"))
      (node (ref "R134") (pin "2") (pinfunction "2_2") (pintype "passive"))
    )
    (net (code "51") (name "Net-(C170-Pad1)") (class "Default")
      (node (ref "C170") (pin "1") (pinfunction "1_1") (pintype "passive"))
      (node (ref "C177") (pin "1") (pinfunction "1_1") (pintype "passive"))
      (node (ref "L10") (pin "2") (pinfunction "2_2") (pintype "passive"))
      (node (ref "L9") (pin "3") (pinfunction "3_3") (pintype "passive"))
      (node (ref "R135") (pin "2") (pinfunction "2_2") (pintype "passive"))
    )
    (net (code "52") (name "Net-(D32-A)") (class "Default")
      (node (ref "D32") (pin "2") (pinfunction "A_2") (pintype "passive"))
      (node (ref "K1") (pin "A2") (pinfunction "A2_A2") (pintype "passive"))
      (node (ref "Q5") (pin "2") (pinfunction "D_2") (pintype "passive"))
      (node (ref "Q5") (pin "4") (pinfunction "D_4") (pintype "passive"))
    )
    (net (code "53") (name "Net-(F1-Pad2)") (class "Default")
      (node (ref "F1") (pin "2") (pinfunction "2_2") (pintype "passive"))
      (node (ref "J19") (pin "1") (pinfunction "1_1") (pintype "passive"))
      (node (ref "J9") (pin "2") (pinfunction "2_2") (pintype "passive"))
      (node (ref "TP60") (pin "1") (pintype "passive"))
    )
    (net (code "54") (name "Net-(F2-Pad1)") (class "Default")
      (node (ref "F2") (pin "1") (pinfunction "1_1") (pintype "passive"))
      (node (ref "L10") (pin "1") (pinfunction "1_1") (pintype "passive"))
      (node (ref "R119") (pin "2") (pinfunction "2_2") (pintype "passive"))
      (node (ref "R126") (pin "1") (pinfunction "1_1") (pintype "passive"))
      (node (ref "R131") (pin "1") (pinfunction "1_1") (pintype "passive"))
      (node (ref "R132") (pin "1") (pinfunction "1_1") (pintype "passive"))
      (node (ref "R133") (pin "1") (pinfunction "1_1") (pintype "passive"))
      (node (ref "TP38") (pin "1") (pintype "passive"))
    )
    (net (code "55") (name "Net-(F2-Pad2)") (class "Default")
      (node (ref "F2") (pin "2") (pinfunction "2_2") (pintype "passive"))
      (node (ref "J20") (pin "1") (pinfunction "1_1") (pintype "passive"))
      (node (ref "J9") (pin "3") (pinfunction "3_3") (pintype "passive"))
      (node (ref "TP59") (pin "1") (pintype "passive"))
    )
    (net (code "56") (name "Net-(K1-Pad14)") (class "Default")
      (node (ref "K1") (pin "14") (pinfunction "14_14") (pintype "passive"))
      (node (ref "K1") (pin "7") (pinfunction "7_7") (pintype "passive"))
      (node (ref "L9") (pin "1") (pinfunction "1_1") (pintype "passive"))
      (node (ref "R146") (pin "1") (pinfunction "1_1") (pintype "passive"))
    )
    (net (code "57") (name "Net-(Q5-G)") (class "Default")
      (node (ref "C200") (pin "1") (pinfunction "1_1") (pintype "passive"))
      (node (ref "Q5") (pin "1") (pinfunction "G_1") (pintype "passive"))
      (node (ref "R151") (pin "2") (pinfunction "2_2") (pintype "passive"))
      (node (ref "R157") (pin "2") (pinfunction "2_2") (pintype "passive"))
    )
    (net (code "58") (name "Net-(R120-Pad1)") (class "Default")
      (node (ref "R120") (pin "1") (pinfunction "1_1") (pintype "passive"))
      (node (ref "R121") (pin "2") (pinfunction "2_2") (pintype "passive"))
    )
    (net (code "59") (name "Net-(R121-Pad1)") (class "Default")
      (node (ref "R121") (pin "1") (pinfunction "1_1") (pintype "passive"))
      (node (ref "R130") (pin "2") (pinfunction "2_2") (pintype "passive"))
    )
    (net (code "60") (name "Net-(R122-Pad1)") (class "Default")
      (node (ref "R122") (pin "1") (pinfunction "1_1") (pintype "passive"))
      (node (ref "R123") (pin "1") (pinfunction "1_1") (pintype "passive"))
      (node (ref "R124") (pin "1") (pinfunction "1_1") (pintype "passive"))
      (node (ref "R127") (pin "2") (pinfunction "2_2") (pintype "passive"))
      (node (ref "R128") (pin "2") (pinfunction "2_2") (pintype "passive"))
      (node (ref "R129") (pin "2") (pinfunction "2_2") (pintype "passive"))
    )
    (net (code "61") (name "Net-(R127-Pad1)") (class "Default")
      (node (ref "R127") (pin "1") (pinfunction "1_1") (pintype "passive"))
      (node (ref "R128") (pin "1") (pinfunction "1_1") (pintype "passive"))
      (node (ref "R129") (pin "1") (pinfunction "1_1") (pintype "passive"))
      (node (ref "R131") (pin "2") (pinfunction "2_2") (pintype "passive"))
      (node (ref "R132") (pin "2") (pinfunction "2_2") (pintype "passive"))
      (node (ref "R133") (pin "2") (pinfunction "2_2") (pintype "passive"))
    )
    (net (code "62") (name "Net-(R134-Pad1)") (class "Default")
      (node (ref "R134") (pin "1") (pinfunction "1_1") (pintype "passive"))
      (node (ref "R136") (pin "2") (pinfunction "2_2") (pintype "passive"))
    )
    (net (code "63") (name "Net-(R135-Pad1)") (class "Default")
      (node (ref "R135") (pin "1") (pinfunction "1_1") (pintype "passive"))
      (node (ref "R137") (pin "2") (pinfunction "2_2") (pintype "passive"))
    )
    (net (code "64") (name "Net-(U28-DCDC_IN)") (class "Default")
      (node (ref "C201") (pin "1") (pinfunction "1_1") (pintype "passive"))
      (node (ref "U28") (pin "13") (pinfunction "LDO_OUT_13") (pintype "output"))
      (node (ref "U28") (pin "16") (pinfunction "DCDC_IN_16") (pintype "power_in"))
    )
    (net (code "65") (name "Net-(U28-DCDC_OUT)") (class "Default")
      (node (ref "C187") (pin "2") (pinfunction "2_2") (pintype "passive"))
      (node (ref "C188") (pin "2") (pinfunction "2_2") (pintype "passive"))
      (node (ref "C189") (pin "2") (pinfunction "2_2") (pintype "passive"))
      (node (ref "U28") (pin "1") (pinfunction "DCDC_OUT_1") (pintype "output"))
      (node (ref "U28") (pin "3") (pinfunction "HLDO_IN_3") (pintype "power_in"))
    )
    (net (code "66") (name "Net-(U28-DIAG)") (class "Default")
      (node (ref "R149") (pin "1") (pinfunction "1_1") (pintype "passive"))
      (node (ref "U28") (pin "14") (pinfunction "DIAG_14") (pintype "output"))
    )
    (net (code "67") (name "Net-(U28-HLDO_OUT)") (class "Default")
      (node (ref "C185") (pin "2") (pinfunction "2_2") (pintype "passive"))
      (node (ref "C186") (pin "2") (pinfunction "2_2") (pintype "passive"))
      (node (ref "U28") (pin "5") (pinfunction "HLDO_OUT_5") (pintype "output"))
    )
    (net (code "68") (name "Net-(U28-INP)") (class "Default")
      (node (ref "C184") (pin "2") (pinfunction "2_2") (pintype "passive"))
      (node (ref "R137") (pin "1") (pinfunction "1_1") (pintype "passive"))
      (node (ref "R139") (pin "1") (pinfunction "1_1") (pintype "passive"))
      (node (ref "U28") (pin "6") (pinfunction "INP_6") (pintype "input"))
    )
    (net (code "69") (name "Net-(U28-OUTN)") (class "Default")
      (node (ref "R159") (pin "1") (pinfunction "1_1") (pintype "passive"))
      (node (ref "U28") (pin "10") (pinfunction "OUTN_10") (pintype "output"))
    )
    (net (code "70") (name "Net-(U28-OUTP)") (class "Default")
      (node (ref "R154") (pin "1") (pinfunction "1_1") (pintype "passive"))
      (node (ref "U28") (pin "11") (pinfunction "OUTP_11") (pintype "output"))
    )
    (net (code "71") (name "Net-(U28-VDD)") (class "Default")
      (node (ref "C204") (pin "1") (pinfunction "1_1") (pintype "passive"))
      (node (ref "C205") (pin "1") (pinfunction "1_1") (pintype "passive"))
      (node (ref "FB13") (pin "2") (pinfunction "2_2") (pintype "passive"))
      (node (ref "R149") (pin "2") (pinfunction "2_2") (pintype "passive"))
      (node (ref "U28") (pin "12") (pinfunction "VDD_12") (pintype "power_in"))
    )
    (net (code "72") (name "Net-(U29-VDD1)") (class "Default")
      (node (ref "C195") (pin "1") (pinfunction "1_1") (pintype "passive"))
      (node (ref "FB8") (pin "2") (pinfunction "2_2") (pintype "passive"))
      (node (ref "U29") (pin "1") (pinfunction "VDD1_1") (pintype "power_in"))
    )
    (net (code "73") (name "Net-(U29-VDD2)") (class "Default")
      (node (ref "C197") (pin "1") (pinfunction "1_1") (pintype "passive"))
      (node (ref "FB10") (pin "2") (pinfunction "2_2") (pintype "passive"))
      (node (ref "U29") (pin "8") (pinfunction "VDD2_8") (pintype "power_in"))
    )
    (net (code "74") (name "Net-(U29-VINN)") (class "Default")
      (node (ref "C190") (pin "1") (pinfunction "1_1") (pintype "passive"))
      (node (ref "R144") (pin "2") (pinfunction "2_2") (pintype "passive"))
      (node (ref "U29") (pin "3") (pinfunction "VINN_3") (pintype "input"))
    )
    (net (code "75") (name "Net-(U29-VINP)") (class "Default")
      (node (ref "C190") (pin "2") (pinfunction "2_2") (pintype "passive"))
      (node (ref "R143") (pin "2") (pinfunction "2_2") (pintype "passive"))
      (node (ref "U29") (pin "2") (pinfunction "VINP_2") (pintype "input"))
    )
    (net (code "76") (name "Net-(U29-VOUTN)") (class "Default")
      (node (ref "R155") (pin "2") (pinfunction "2_2") (pintype "passive"))
      (node (ref "U29") (pin "6") (pinfunction "VOUTN_6") (pintype "output"))
    )
    (net (code "77") (name "Net-(U29-VOUTP)") (class "Default")
      (node (ref "R158") (pin "2") (pinfunction "2_2") (pintype "passive"))
      (node (ref "U29") (pin "7") (pinfunction "VOUTP_7") (pintype "output"))
    )
    (net (code "78") (name "Net-(U30-VDD1)") (class "Default")
      (node (ref "C193") (pin "1") (pinfunction "1_1") (pintype "passive"))
      (node (ref "FB7") (pin "2") (pinfunction "2_2") (pintype "passive"))
      (node (ref "U30") (pin "1") (pinfunction "VDD1_1") (pintype "power_in"))
    )
    (net (code "79") (name "Net-(U30-VDD2)") (class "Default")
      (node (ref "C198") (pin "1") (pinfunction "1_1") (pintype "passive"))
      (node (ref "FB11") (pin "2") (pinfunction "2_2") (pintype "passive"))
      (node (ref "U30") (pin "8") (pinfunction "VDD2_8") (pintype "power_in"))
    )
    (net (code "80") (name "Net-(U30-VINP)") (class "Default")
      (node (ref "C182") (pin "1") (pinfunction "1_1") (pintype "passive"))
      (node (ref "R130") (pin "1") (pinfunction "1_1") (pintype "passive"))
      (node (ref "R138") (pin "2") (pinfunction "2_2") (pintype "passive"))
      (node (ref "U30") (pin "2") (pinfunction "VINP_2") (pintype "input"))
    )
    (net (code "81") (name "Net-(U30-VOUTN)") (class "Default")
      (node (ref "R156") (pin "2") (pinfunction "2_2") (pintype "passive"))
      (node (ref "U30") (pin "6") (pinfunction "VOUTN_6") (pintype "output"))
    )
    (net (code "82") (name "Net-(U30-VOUTP)") (class "Default")
      (node (ref "R160") (pin "2") (pinfunction "2_2") (pintype "passive"))
      (node (ref "U30") (pin "7") (pinfunction "VOUTP_7") (pintype "output"))
    )
    (net (code "83") (name "Net-(U31-VDD1)") (class "Default")
      (node (ref "C191") (pin "2") (pinfunction "2_2") (pintype "passive"))
      (node (ref "FB6") (pin "2") (pinfunction "2_2") (pintype "passive"))
      (node (ref "U31") (pin "1") (pinfunction "VDD1_1") (pintype "power_in"))
    )
    (net (code "84") (name "Net-(U31-VDD2)") (class "Default")
      (node (ref "C199") (pin "1") (pinfunction "1_1") (pintype "passive"))
      (node (ref "FB12") (pin "2") (pinfunction "2_2") (pintype "passive"))
      (node (ref "U31") (pin "8") (pinfunction "VDD2_8") (pintype "power_in"))
    )
    (net (code "85") (name "Net-(U31-VINN)") (class "Default")
      (node (ref "C183") (pin "2") (pinfunction "2_2") (pintype "passive"))
      (node (ref "R141") (pin "2") (pinfunction "2_2") (pintype "passive"))
      (node (ref "U31") (pin "3") (pinfunction "VINN_3") (pintype "input"))
    )
    (net (code "86") (name "Net-(U31-VINP)") (class "Default")
      (node (ref "C183") (pin "1") (pinfunction "1_1") (pintype "passive"))
      (node (ref "R142") (pin "2") (pinfunction "2_2") (pintype "passive"))
      (node (ref "U31") (pin "2") (pinfunction "VINP_2") (pintype "input"))
    )
    (net (code "87") (name "Net-(U31-VOUTN)") (class "Default")
      (node (ref "R161") (pin "2") (pinfunction "2_2") (pintype "passive"))
      (node (ref "U31") (pin "6") (pinfunction "VOUTN_6") (pintype "output"))
    )
    (net (code "88") (name "Net-(U31-VOUTP)") (class "Default")
      (node (ref "R162") (pin "2") (pinfunction "2_2") (pintype "passive"))
      (node (ref "U31") (pin "7") (pinfunction "VOUTP_7") (pintype "output"))
    )
    (net (code "89") (name "Net-(U32-IN+)") (class "Default")
      (node (ref "L10") (pin "4") (pinfunction "4_4") (pintype "passive"))
      (node (ref "R126") (pin "2") (pinfunction "2_2") (pintype "passive"))
      (node (ref "U32") (pin "1") (pinfunction "IN+_1") (pintype "passive"))
    )
    (net (code "90") (name "Net-(U32-IN-)") (class "Default")
      (node (ref "F1") (pin "1") (pinfunction "1_1") (pintype "passive"))
      (node (ref "R118") (pin "1") (pinfunction "1_1") (pintype "passive"))
      (node (ref "R122") (pin "2") (pinfunction "2_2") (pintype "passive"))
      (node (ref "R123") (pin "2") (pinfunction "2_2") (pintype "passive"))
      (node (ref "R124") (pin "2") (pinfunction "2_2") (pintype "passive"))
      (node (ref "TP35") (pin "1") (pintype "passive"))
      (node (ref "U32") (pin "2") (pinfunction "IN-_2") (pintype "passive"))
    )
    (net (code "91") (name "Net-(U32-VOC)") (class "Default")
      (node (ref "C196") (pin "1") (pinfunction "1_1") (pintype "passive"))
      (node (ref "R145") (pin "1") (pinfunction "1_1") (pintype "passive"))
      (node (ref "R147") (pin "1") (pinfunction "1_1") (pintype "passive"))
      (node (ref "U32") (pin "9") (pinfunction "VOC_9") (pintype "passive"))
    )
    (net (code "92") (name "Net-(U32-VOUT)") (class "Default")
      (node (ref "R150") (pin "2") (pinfunction "2_2") (pintype "passive"))
      (node (ref "U32") (pin "6") (pinfunction "VOUT_6") (pintype "passive"))
    )
    (net (code "93") (name "Net-(U32-VREF)") (class "Default")
      (node (ref "C194") (pin "2") (pinfunction "2_2") (pintype "passive"))
      (node (ref "R148") (pin "2") (pinfunction "2_2") (pintype "passive"))
      (node (ref "U32") (pin "5") (pinfunction "VREF_5") (pintype "passive"))
    )
    (net (code "94") (name "Net-(U32-VS)") (class "Default")
      (node (ref "C192") (pin "2") (pinfunction "2_2") (pintype "passive"))
      (node (ref "FB9") (pin "1") (pinfunction "1_1") (pintype "passive"))
      (node (ref "U32") (pin "8") (pinfunction "VS_8") (pintype "power_in"))
    )
    (net (code "95") (name "Net-(U32-~{FAULT})") (class "Default")
      (node (ref "C202") (pin "1") (pinfunction "1_1") (pintype "passive"))
      (node (ref "R152") (pin "1") (pinfunction "1_1") (pintype "passive"))
      (node (ref "TP41") (pin "1") (pintype "passive"))
      (node (ref "U32") (pin "4") (pinfunction "~{FAULT}_4") (pintype "output"))
    )
    (net (code "96") (name "Net-(U32-~{OC})") (class "Default")
      (node (ref "C203") (pin "1") (pinfunction "1_1") (pintype "passive"))
      (node (ref "R153") (pin "2") (pinfunction "2_2") (pintype "passive"))
      (node (ref "TP42") (pin "1") (pintype "passive"))
      (node (ref "U32") (pin "7") (pinfunction "~{OC}_7") (pintype "open_collector"))
    )
    (net (code "97") (name "Net-(U33A-A)") (class "Default")
      (node (ref "C210") (pin "1") (pinfunction "1_1") (pintype "passive"))
      (node (ref "R168") (pin "2") (pinfunction "2_2") (pintype "passive"))
      (node (ref "R176") (pin "2") (pinfunction "2_2") (pintype "passive"))
      (node (ref "U33") (pin "1") (pinfunction "A_1") (pintype "input"))
    )
    (net (code "98") (name "Net-(U33A-B)") (class "Default")
      (node (ref "C209") (pin "1") (pinfunction "1_1") (pintype "passive"))
      (node (ref "R173") (pin "2") (pinfunction "2_2") (pintype "passive"))
      (node (ref "R177") (pin "2") (pinfunction "2_2") (pintype "passive"))
      (node (ref "U33") (pin "2") (pinfunction "B_2") (pintype "input"))
    )
    (net (code "99") (name "Net-(U34A-A)") (class "Default")
      (node (ref "C212") (pin "1") (pinfunction "1_1") (pintype "passive"))
      (node (ref "R169") (pin "2") (pinfunction "2_2") (pintype "passive"))
      (node (ref "R178") (pin "2") (pinfunction "2_2") (pintype "passive"))
      (node (ref "U34") (pin "1") (pinfunction "A_1") (pintype "input"))
    )
    (net (code "100") (name "Net-(U34A-B)") (class "Default")
      (node (ref "C211") (pin "1") (pinfunction "1_1") (pintype "passive"))
      (node (ref "R172") (pin "2") (pinfunction "2_2") (pintype "passive"))
      (node (ref "R179") (pin "2") (pinfunction "2_2") (pintype "passive"))
      (node (ref "U34") (pin "2") (pinfunction "B_2") (pintype "input"))
    )
    (net (code "101") (name "Net-(U35A-Y)") (class "Default")
      (node (ref "R170") (pin "1") (pinfunction "1_1") (pintype "passive"))
      (node (ref "U35") (pin "4") (pinfunction "Y_4") (pintype "output"))
    )
    (net (code "102") (name "unconnected-(J16-MNT_1-Pad2)") (class "Default")
      (node (ref "J16") (pin "2") (pinfunction "MNT_1_2") (pintype "passive"))
    )
    (net (code "103") (name "unconnected-(J16-MNT_2-Pad3)") (class "Default")
      (node (ref "J16") (pin "3") (pinfunction "MNT_2_3") (pintype "passive"))
    )
    (net (code "104") (name "unconnected-(J16-MNT_3-Pad4)") (class "Default")
      (node (ref "J16") (pin "4") (pinfunction "MNT_3_4") (pintype "passive"))
    )
    (net (code "105") (name "unconnected-(J16-MNT_4-Pad5)") (class "Default")
      (node (ref "J16") (pin "5") (pinfunction "MNT_4_5") (pintype "passive"))
    )
    (net (code "106") (name "unconnected-(J17-MNT_1-Pad2)") (class "Default")
      (node (ref "J17") (pin "2") (pinfunction "MNT_1_2") (pintype "passive"))
    )
    (net (code "107") (name "unconnected-(J17-MNT_2-Pad3)") (class "Default")
      (node (ref "J17") (pin "3") (pinfunction "MNT_2_3") (pintype "passive"))
    )
    (net (code "108") (name "unconnected-(J17-MNT_3-Pad4)") (class "Default")
      (node (ref "J17") (pin "4") (pinfunction "MNT_3_4") (pintype "passive"))
    )
    (net (code "109") (name "unconnected-(J17-MNT_4-Pad5)") (class "Default")
      (node (ref "J17") (pin "5") (pinfunction "MNT_4_5") (pintype "passive"))
    )
    (net (code "110") (name "unconnected-(J18-MNT_1-Pad2)") (class "Default")
      (node (ref "J18") (pin "2") (pinfunction "MNT_1_2") (pintype "passive+no_connect"))
    )
    (net (code "111") (name "unconnected-(J18-MNT_2-Pad3)") (class "Default")
      (node (ref "J18") (pin "3") (pinfunction "MNT_2_3") (pintype "passive+no_connect"))
    )
    (net (code "112") (name "unconnected-(J18-MNT_3-Pad4)") (class "Default")
      (node (ref "J18") (pin "4") (pinfunction "MNT_3_4") (pintype "passive+no_connect"))
    )
    (net (code "113") (name "unconnected-(J18-MNT_4-Pad5)") (class "Default")
      (node (ref "J18") (pin "5") (pinfunction "MNT_4_5") (pintype "passive+no_connect"))
    )
    (net (code "114") (name "unconnected-(J19-MNT_1-Pad2)") (class "Default")
      (node (ref "J19") (pin "2") (pinfunction "MNT_1_2") (pintype "passive+no_connect"))
    )
    (net (code "115") (name "unconnected-(J19-MNT_2-Pad3)") (class "Default")
      (node (ref "J19") (pin "3") (pinfunction "MNT_2_3") (pintype "passive+no_connect"))
    )
    (net (code "116") (name "unconnected-(J19-MNT_3-Pad4)") (class "Default")
      (node (ref "J19") (pin "4") (pinfunction "MNT_3_4") (pintype "passive+no_connect"))
    )
    (net (code "117") (name "unconnected-(J19-MNT_4-Pad5)") (class "Default")
      (node (ref "J19") (pin "5") (pinfunction "MNT_4_5") (pintype "passive+no_connect"))
    )
    (net (code "118") (name "unconnected-(J20-Pad2)") (class "Default")
      (node (ref "J20") (pin "2") (pinfunction "2_2") (pintype "passive+no_connect"))
    )
    (net (code "119") (name "unconnected-(J20-Pad3)") (class "Default")
      (node (ref "J20") (pin "3") (pinfunction "3_3") (pintype "passive+no_connect"))
    )
    (net (code "120") (name "unconnected-(J20-Pad4)") (class "Default")
      (node (ref "J20") (pin "4") (pinfunction "4_4") (pintype "passive+no_connect"))
    )
    (net (code "121") (name "unconnected-(J20-Pad5)") (class "Default")
      (node (ref "J20") (pin "5") (pinfunction "5_5") (pintype "passive+no_connect"))
    )
    (net (code "122") (name "unconnected-(K1-Pad5)") (class "Default")
      (node (ref "K1") (pin "5") (pinfunction "5_5") (pintype "passive+no_connect"))
    )
    (net (code "123") (name "unconnected-(K1-Pad12)") (class "Default")
      (node (ref "K1") (pin "12") (pinfunction "12_12") (pintype "passive+no_connect"))
    )
    (net (code "124") (name "unconnected-(MP6-Pad1)") (class "Default")
      (node (ref "MP6") (pin "1") (pinfunction "1_1") (pintype "passive+no_connect"))
    )
    (net (code "125") (name "unconnected-(MP7-Pad1)") (class "Default")
      (node (ref "MP7") (pin "1") (pinfunction "1_1") (pintype "passive+no_connect"))
    )
    (net (code "126") (name "unconnected-(MP8-Pad1)") (class "Default")
      (node (ref "MP8") (pin "1") (pinfunction "1_1") (pintype "passive+no_connect"))
    )
    (net (code "127") (name "unconnected-(MP11-Pad1)") (class "Default")
      (node (ref "MP11") (pin "1") (pinfunction "1_1") (pintype "passive+no_connect"))
    )
    (net (code "128") (name "unconnected-(MP12-Pad1)") (class "Default")
      (node (ref "MP12") (pin "1") (pinfunction "1_1") (pintype "passive+no_connect"))
    )
    (net (code "129") (name "unconnected-(MP13-Pad1)") (class "Default")
      (node (ref "MP13") (pin "1") (pinfunction "1_1") (pintype "passive+no_connect"))
    )
    (net (code "130") (name "unconnected-(U28-NC-Pad4)") (class "Default")
      (node (ref "U28") (pin "4") (pinfunction "NC_4") (pintype "passive+no_connect"))
    )
    (net (code "131") (name "unconnected-(U32-NC-Pad10)") (class "Default")
      (node (ref "U32") (pin "10") (pinfunction "NC_10") (pintype "passive+no_connect"))
    )
    (net (code "132") (name "unconnected-(U35B-NC-Pad1)") (class "Default")
      (node (ref "U35") (pin "1") (pinfunction "NC_1") (pintype "passive+no_connect"))
    )
  )
)
